# OBCv4_24.net
KiCad netlist of a schematic drawn in EAGLE
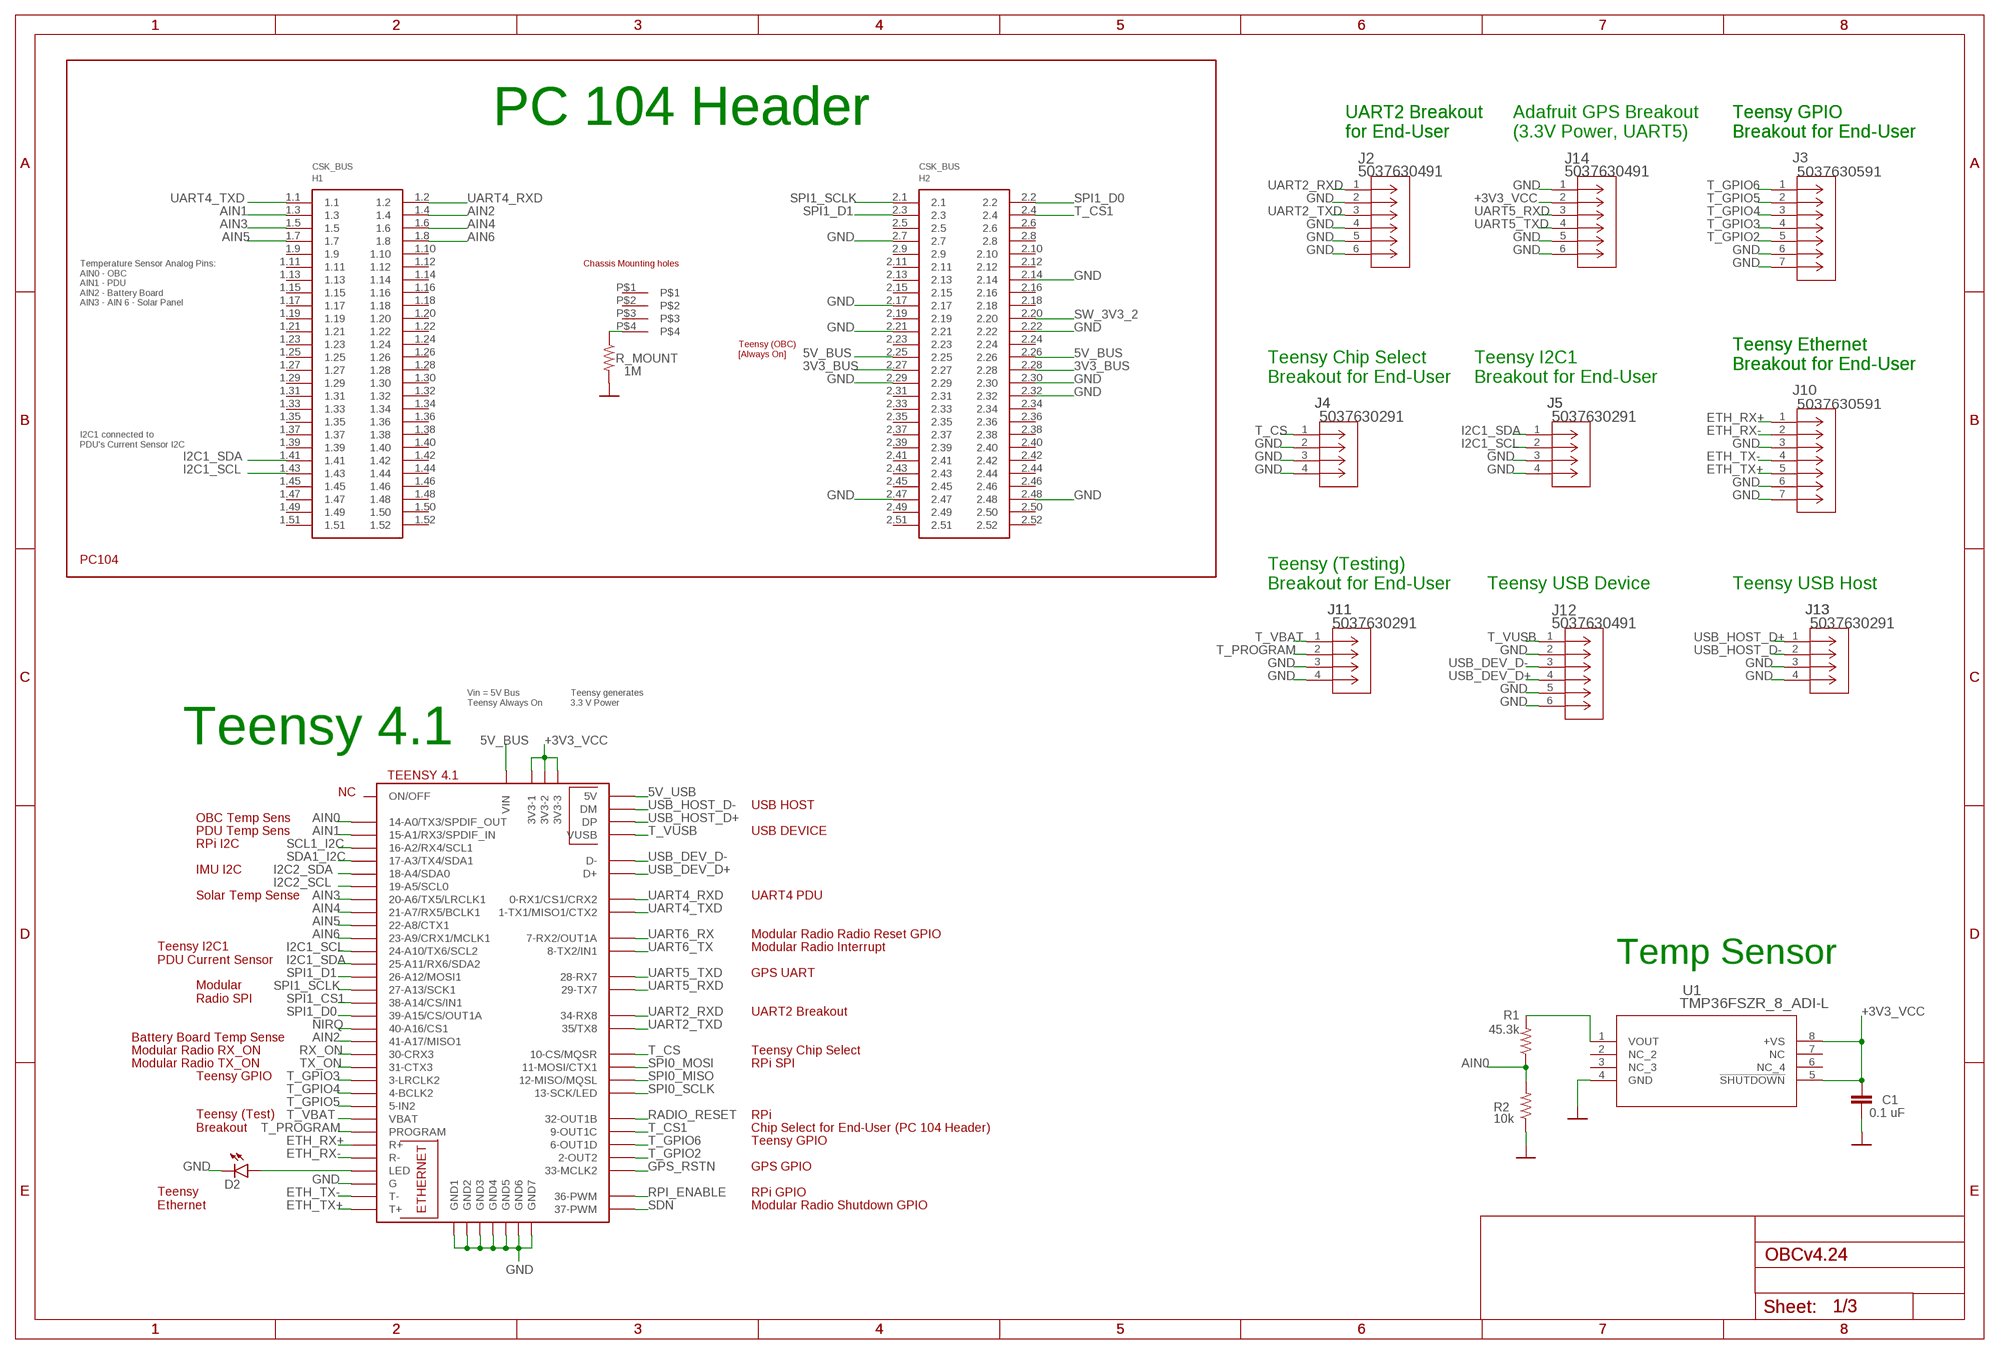
[diagram p0: schematic, sheet 1]
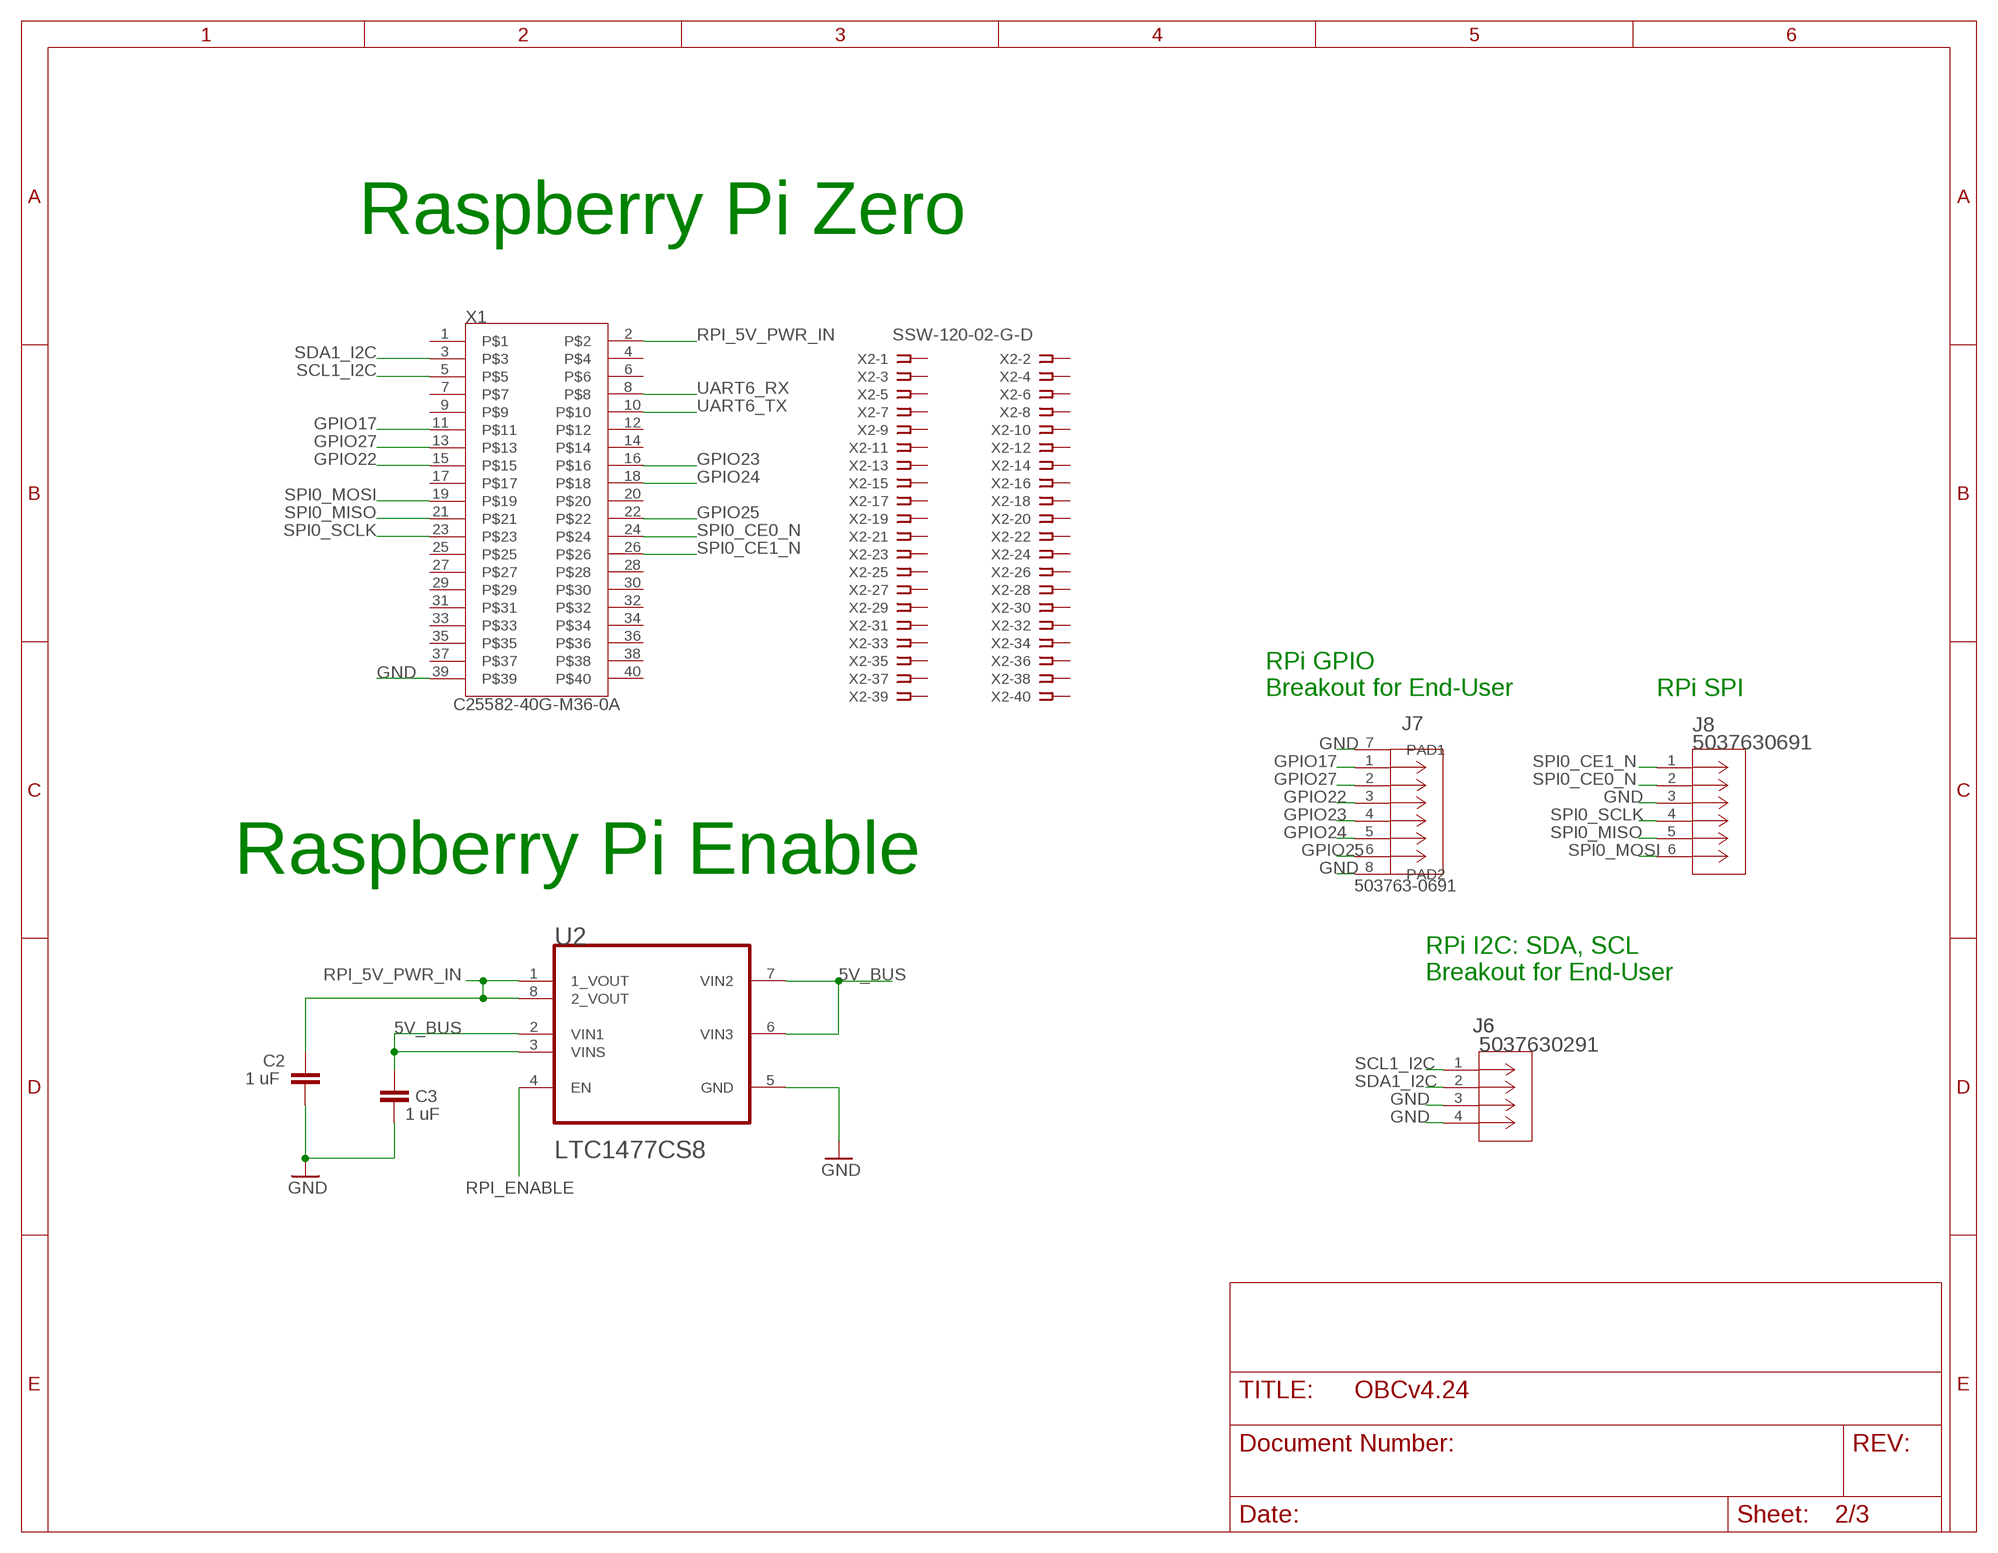
[diagram p1: schematic, sheet 2]
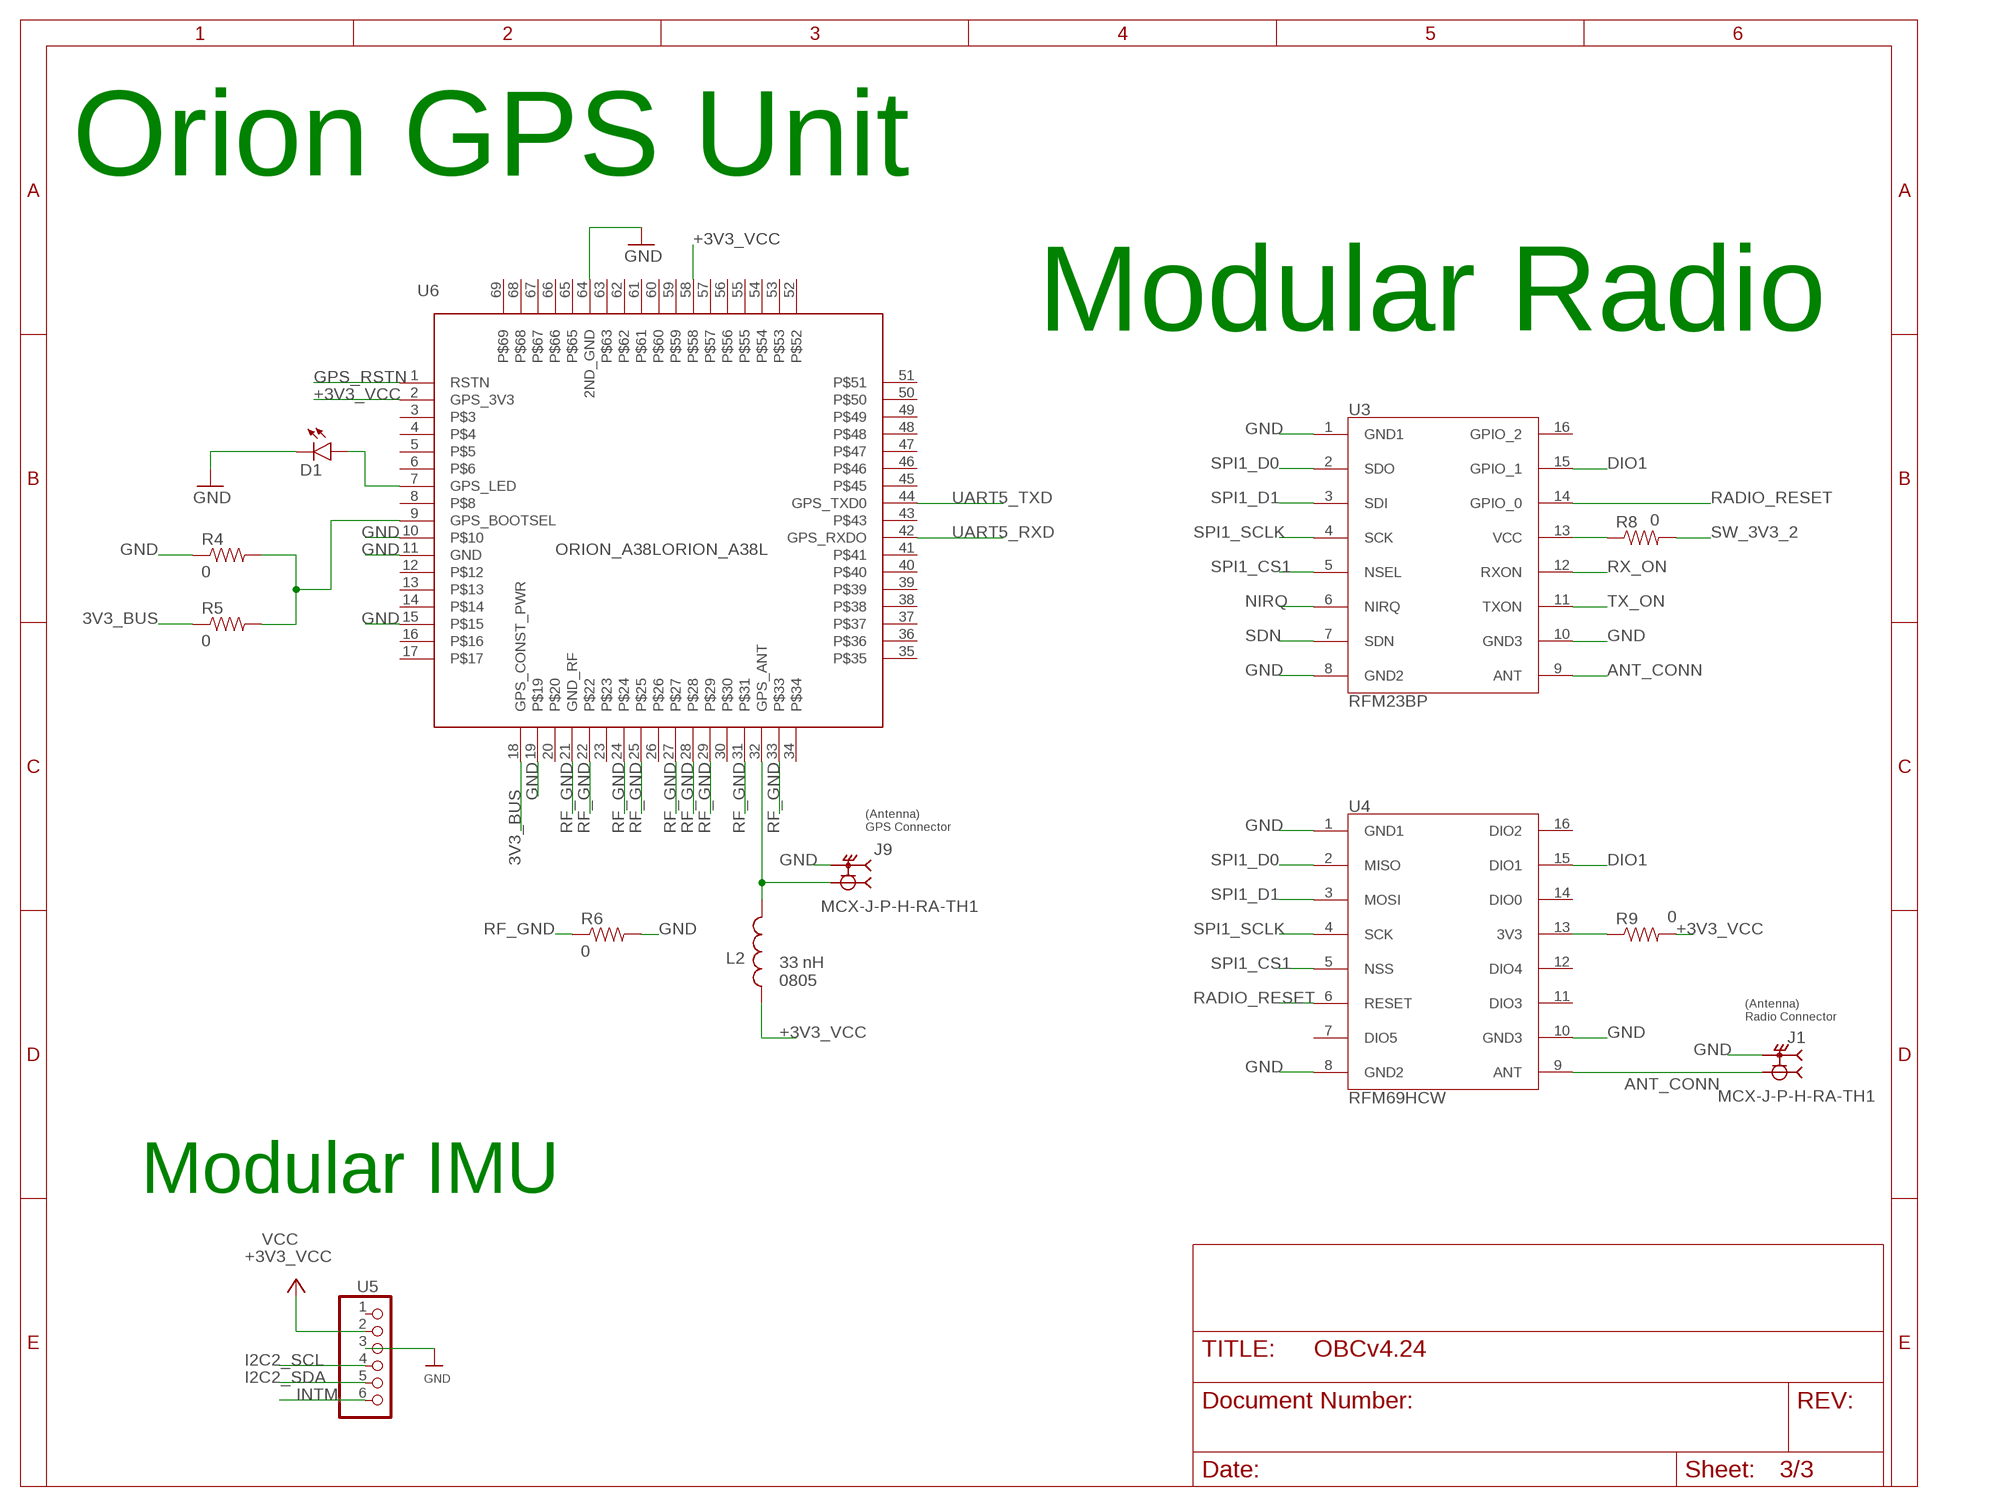
[diagram p2: schematic, sheet 3]

(export (version "E")
  (design (tool "Eeschema 10.0.6"))
  (components
    (comp (ref "D1")
      (value "LEDCHIP-LED0603")
      (footprint "eagle-import:CHIP-LED0603")
      (libsource (lib "eagle-import") (part "LEDCHIP-LED0603"))
    )
    (comp (ref "J1")
      (value "MCX-J-P-H-RA-TH1")
      (footprint "eagle-import:SAMTEC_MCX-J-P-H-RA-TH1")
      (fields (field (name "DIGI-KEY_PART_NUMBER") "SAM10607-ND") (field (name "MF") "Samtec"))
      (libsource (lib "eagle-import") (part "MCX-J-P-H-RA-TH1"))
    )
    (comp (ref "J9")
      (value "MCX-J-P-H-RA-TH1")
      (footprint "eagle-import:SAMTEC_MCX-J-P-H-RA-TH1")
      (fields (field (name "DIGI-KEY_PART_NUMBER") "SAM10607-ND") (field (name "MF") "Samtec"))
      (libsource (lib "eagle-import") (part "MCX-J-P-H-RA-TH1"))
    )
    (comp (ref "L2")
      (value "AIMC-0805-2N2S-T")
      (footprint "eagle-import:INDC2012X105N")
      (fields (field (name "DIGI-KEY_PART_NUMBER") "535-11562-1-ND") (field (name "MF") "Abracon"))
      (libsource (lib "eagle-import") (part "AIMC-0805-2N2S-T"))
    )
    (comp (ref "R4")
      (value "0")
      (footprint "eagle-import:0805")
      (libsource (lib "eagle-import") (part "RESISTOR0805-RES"))
    )
    (comp (ref "R5")
      (value "0")
      (footprint "eagle-import:0805")
      (libsource (lib "eagle-import") (part "RESISTOR0805-RES"))
    )
    (comp (ref "R6")
      (value "0")
      (footprint "eagle-import:0805")
      (libsource (lib "eagle-import") (part "RESISTOR0805-RES"))
    )
    (comp (ref "R8")
      (value "0")
      (footprint "eagle-import:R2512")
      (libsource (lib "eagle-import") (part "RESISTOR2512"))
    )
    (comp (ref "R9")
      (value "0")
      (footprint "eagle-import:R2512")
      (libsource (lib "eagle-import") (part "RESISTOR2512"))
    )
    (comp (ref "U3")
      (value "RFM23BP")
      (footprint "eagle-import:RFM23BP")
      (libsource (lib "eagle-import") (part "RFM23BP"))
    )
    (comp (ref "U4")
      (value "RFM69HCW")
      (footprint "eagle-import:RFM69HCW")
      (libsource (lib "eagle-import") (part "RFM69HCW"))
    )
    (comp (ref "U5")
      (value "HEADER-1X670MIL")
      (footprint "eagle-import:1X06_ROUND_70")
      (libsource (lib "eagle-import") (part "HEADER-1X670MIL"))
    )
    (comp (ref "U6")
      (value "ORION_A38LORION_A38L")
      (footprint "eagle-import:ORION_A38L")
      (libsource (lib "eagle-import") (part "ORION_A38LORION_A38L"))
    )
    (comp (ref "C1")
      (value "0.1 uF")
      (footprint "eagle-import:0805")
      (libsource (lib "eagle-import") (part "CAP0805"))
    )
    (comp (ref "D2")
      (value "LEDCHIP-LED0603")
      (footprint "eagle-import:CHIP-LED0603")
      (libsource (lib "eagle-import") (part "LEDCHIP-LED0603"))
    )
    (comp (ref "H1")
      (value "PC104_WCONN")
      (footprint "eagle-import:PC104_WCONN")
      (libsource (lib "eagle-import") (part "PC104_WCONN"))
    )
    (comp (ref "J2")
      (value "5037630491")
      (footprint "eagle-import:CON_5037630491")
      (fields (field (name "COPYRIGHT") "Copyright (C) 2018 Accelerated Designs. All rights reserved"))
      (libsource (lib "eagle-import") (part "5037630491"))
    )
    (comp (ref "J3")
      (value "5037630591")
      (footprint "eagle-import:CON_5037630591")
      (fields (field (name "COPYRIGHT") "Copyright (C) 2021 Ultra Librarian. All rights reserved."))
      (libsource (lib "eagle-import") (part "5037630591"))
    )
    (comp (ref "J4")
      (value "5037630291")
      (footprint "eagle-import:CON_5037630291")
      (fields (field (name "COPYRIGHT") "Copyright (C) 2018 Accelerated Designs. All rights reserved"))
      (libsource (lib "eagle-import") (part "5037630291"))
    )
    (comp (ref "J5")
      (value "5037630291")
      (footprint "eagle-import:CON_5037630291")
      (fields (field (name "COPYRIGHT") "Copyright (C) 2018 Accelerated Designs. All rights reserved"))
      (libsource (lib "eagle-import") (part "5037630291"))
    )
    (comp (ref "J10")
      (value "5037630591")
      (footprint "eagle-import:CON_5037630591")
      (fields (field (name "COPYRIGHT") "Copyright (C) 2021 Ultra Librarian. All rights reserved."))
      (libsource (lib "eagle-import") (part "5037630591"))
    )
    (comp (ref "J11")
      (value "5037630291")
      (footprint "eagle-import:CON_5037630291")
      (fields (field (name "COPYRIGHT") "Copyright (C) 2018 Accelerated Designs. All rights reserved"))
      (libsource (lib "eagle-import") (part "5037630291"))
    )
    (comp (ref "J12")
      (value "5037630491")
      (footprint "eagle-import:CON_5037630491")
      (fields (field (name "COPYRIGHT") "Copyright (C) 2018 Accelerated Designs. All rights reserved"))
      (libsource (lib "eagle-import") (part "5037630491"))
    )
    (comp (ref "J13")
      (value "5037630291")
      (footprint "eagle-import:CON_5037630291")
      (fields (field (name "COPYRIGHT") "Copyright (C) 2018 Accelerated Designs. All rights reserved"))
      (libsource (lib "eagle-import") (part "5037630291"))
    )
    (comp (ref "J14")
      (value "5037630491")
      (footprint "eagle-import:CON_5037630491")
      (fields (field (name "COPYRIGHT") "Copyright (C) 2018 Accelerated Designs. All rights reserved"))
      (libsource (lib "eagle-import") (part "5037630491"))
    )
    (comp (ref "R1")
      (value "45.3k")
      (footprint "eagle-import:0805")
      (libsource (lib "eagle-import") (part "RESISTOR0805-RES"))
    )
    (comp (ref "R2")
      (value "10k")
      (footprint "eagle-import:0805")
      (libsource (lib "eagle-import") (part "RESISTOR0805-RES"))
    )
    (comp (ref "R_MOUNT")
      (value "1M")
      (footprint "eagle-import:0805")
      (libsource (lib "eagle-import") (part "RESISTOR0805-RES"))
    )
    (comp (ref "U$1")
      (value "TEENSY41TEENSY")
      (footprint "eagle-import:TEENSY41")
      (libsource (lib "eagle-import") (part "TEENSY41TEENSY"))
    )
    (comp (ref "U1")
      (value "TMP36FSZR_8_ADI-L")
      (footprint "eagle-import:R_8_ADI-L")
      (fields
        (field (name "MANUFACTURER_PART_NUMBER") "TMP36FSZ")
        (field (name "COPYRIGHT") "Copyright (C) 2021 Ultra Librarian. All rights reserved.")
      )
      (libsource (lib "eagle-import") (part "TMP36FSZR_8_ADI-L"))
    )
    (comp (ref "C2")
      (value "1 uF")
      (footprint "eagle-import:0805")
      (libsource (lib "eagle-import") (part "CAP0805"))
    )
    (comp (ref "C3")
      (value "1 uF")
      (footprint "eagle-import:0805")
      (libsource (lib "eagle-import") (part "CAP0805"))
    )
    (comp (ref "J6")
      (value "5037630291")
      (footprint "eagle-import:CON_5037630291")
      (fields (field (name "COPYRIGHT") "Copyright (C) 2018 Accelerated Designs. All rights reserved"))
      (libsource (lib "eagle-import") (part "5037630291"))
    )
    (comp (ref "J7")
      (value "503763-0691")
      (footprint "eagle-import:CONN_503763-0691_MOL")
      (fields (field (name "COPYRIGHT") "Copyright (C) 2018 Accelerated Designs. All rights reserved"))
      (libsource (lib "eagle-import") (part "503763-0691"))
    )
    (comp (ref "J8")
      (value "5037630691")
      (footprint "eagle-import:CONN_503763-0691_MOL")
      (fields
        (field (name "MANUFACTURER_PART_NUMBER") "503763-0691")
        (field (name "COPYRIGHT") "Copyright (C) 2018 Accelerated Designs. All rights reserved")
      )
      (libsource (lib "eagle-import") (part "5037630691"))
    )
    (comp (ref "U2")
      (value "LTC1477CS8LINEAR_TECHNOLOGY_LTC1477CS8_0_2")
      (footprint "eagle-import:LINEAR_TECHNOLOGY_LTC1477CS8_2")
      (fields (field (name "MF") "Linear Technology") (field (name "MPN") "LTC1477CS8"))
      (libsource (lib "eagle-import") (part "LTC1477CS8LINEAR_TECHNOLOGY_LTC1477CS8_0_2"))
    )
    (comp (ref "X1")
      (value "C25582-40G-M36-0A")
      (footprint "eagle-import:ADAFRUIT_C25582-40G-M36-0A_0")
      (libsource (lib "eagle-import") (part "C25582-40G-M36-0A"))
    )
    (comp (ref "X2")
      (value "SSW-120-02-G-D")
      (footprint "eagle-import:SSW-120-02-G-D")
      (fields (field (name "MF") "Samtec Inc."))
      (libsource (lib "eagle-import") (part "SSW-120-02-G-D"))
    )
  )
  (nets
    (net (code "1") (name "+3V3_VCC") (class "Default")
      (node (ref "C1") (pin "1") (pinfunction "1_1") (pintype "passive"))
      (node (ref "J14") (pin "2") (pinfunction "2_2") (pintype "passive"))
      (node (ref "L2") (pin "1") (pinfunction "1_1") (pintype "passive"))
      (node (ref "R9") (pin "2") (pinfunction "2_2") (pintype "passive"))
      (node (ref "U$1") (pin "3V3-1") (pinfunction "3V3-1_3V3-1") (pintype "bidirectional"))
      (node (ref "U$1") (pin "3V3-2") (pinfunction "3V3-2_3V3-2") (pintype "bidirectional"))
      (node (ref "U$1") (pin "3V3-3") (pinfunction "3V3-3_3V3-3") (pintype "bidirectional"))
      (node (ref "U1") (pin "5") (pinfunction "~{SHUTDOWN}_5") (pintype "passive"))
      (node (ref "U1") (pin "8") (pinfunction "+VS_8") (pintype "power_in"))
      (node (ref "U5") (pin "2") (pinfunction "2_2") (pintype "passive"))
      (node (ref "U6") (pin "2") (pinfunction "GPS_3V3_2") (pintype "bidirectional"))
      (node (ref "U6") (pin "58") (pinfunction "P$58_58") (pintype "bidirectional"))
    )
    (net (code "2") (name "3V3_BUS") (class "Default")
      (node (ref "H1") (pin "2.27") (pinfunction "2.27_2.27") (pintype "bidirectional"))
      (node (ref "H1") (pin "2.28") (pinfunction "2.28_2.28") (pintype "bidirectional"))
      (node (ref "R5") (pin "1") (pinfunction "1_1") (pintype "passive"))
      (node (ref "U6") (pin "18") (pinfunction "GPS_CONST_PWR_18") (pintype "bidirectional"))
    )
    (net (code "3") (name "5V_BUS") (class "Default")
      (node (ref "C3") (pin "1") (pinfunction "1_1") (pintype "passive"))
      (node (ref "H1") (pin "2.25") (pinfunction "2.25_2.25") (pintype "bidirectional"))
      (node (ref "H1") (pin "2.26") (pinfunction "2.26_2.26") (pintype "bidirectional"))
      (node (ref "U$1") (pin "VIN") (pinfunction "VIN_VIN") (pintype "bidirectional"))
      (node (ref "U2") (pin "2") (pinfunction "VIN1_2") (pintype "power_in"))
      (node (ref "U2") (pin "3") (pinfunction "VINS_3") (pintype "power_in"))
      (node (ref "U2") (pin "6") (pinfunction "VIN3_6") (pintype "power_in"))
      (node (ref "U2") (pin "7") (pinfunction "VIN2_7") (pintype "power_in"))
    )
    (net (code "4") (name "5V_USB") (class "Default")
      (node (ref "U$1") (pin "+5V") (pinfunction "5V_+5V") (pintype "bidirectional"))
    )
    (net (code "5") (name "AIN0") (class "Default")
      (node (ref "R1") (pin "1") (pinfunction "1_1") (pintype "passive"))
      (node (ref "R2") (pin "2") (pinfunction "2_2") (pintype "passive"))
      (node (ref "U$1") (pin "14-A0/TX3/SPDIF_OUT") (pinfunction "14-A0/TX3/SPDIF_OUT_14-A0/TX3/SPDIF_OUT") (pintype "bidirectional"))
    )
    (net (code "6") (name "AIN1") (class "Default")
      (node (ref "H1") (pin "1.3") (pinfunction "1.3_1.3") (pintype "bidirectional"))
      (node (ref "U$1") (pin "15-A1/RX3/SPDIF_IN") (pinfunction "15-A1/RX3/SPDIF_IN_15-A1/RX3/SPDIF_IN") (pintype "bidirectional"))
    )
    (net (code "7") (name "AIN2") (class "Default")
      (node (ref "H1") (pin "1.4") (pinfunction "1.4_1.4") (pintype "bidirectional"))
      (node (ref "U$1") (pin "41-A17/MISO1") (pinfunction "41-A17/MISO1_41-A17/MISO1") (pintype "bidirectional"))
    )
    (net (code "8") (name "AIN3") (class "Default")
      (node (ref "H1") (pin "1.5") (pinfunction "1.5_1.5") (pintype "bidirectional"))
      (node (ref "U$1") (pin "20-A6/TX5/LRCLK1") (pinfunction "20-A6/TX5/LRCLK1_20-A6/TX5/LRCLK1") (pintype "bidirectional"))
    )
    (net (code "9") (name "AIN4") (class "Default")
      (node (ref "H1") (pin "1.6") (pinfunction "1.6_1.6") (pintype "bidirectional"))
      (node (ref "U$1") (pin "21-A7/RX5/BCLK1") (pinfunction "21-A7/RX5/BCLK1_21-A7/RX5/BCLK1") (pintype "bidirectional"))
    )
    (net (code "10") (name "AIN5") (class "Default")
      (node (ref "H1") (pin "1.7") (pinfunction "1.7_1.7") (pintype "bidirectional"))
      (node (ref "U$1") (pin "22-A8/CTX1") (pinfunction "22-A8/CTX1_22-A8/CTX1") (pintype "bidirectional"))
    )
    (net (code "11") (name "AIN6") (class "Default")
      (node (ref "H1") (pin "1.8") (pinfunction "1.8_1.8") (pintype "bidirectional"))
      (node (ref "U$1") (pin "23-A9/CRX1/MCLK1") (pinfunction "23-A9/CRX1/MCLK1_23-A9/CRX1/MCLK1") (pintype "bidirectional"))
    )
    (net (code "12") (name "ANT_CONN") (class "Default")
      (node (ref "J1") (pin "1") (pinfunction "1_1") (pintype "passive"))
      (node (ref "U3") (pin "9") (pinfunction "ANT_9") (pintype "bidirectional"))
      (node (ref "U4") (pin "9") (pinfunction "ANT_9") (pintype "bidirectional"))
    )
    (net (code "13") (name "DIO1") (class "Default")
      (node (ref "U3") (pin "15") (pinfunction "GPIO_1_15") (pintype "bidirectional"))
      (node (ref "U4") (pin "15") (pinfunction "DIO1_15") (pintype "bidirectional"))
    )
    (net (code "14") (name "ETH_RX+") (class "Default")
      (node (ref "J10") (pin "1") (pinfunction "1_1") (pintype "passive"))
      (node (ref "U$1") (pin "R+") (pinfunction "R+_R+") (pintype "bidirectional"))
    )
    (net (code "15") (name "ETH_RX-") (class "Default")
      (node (ref "J10") (pin "2") (pinfunction "2_2") (pintype "passive"))
      (node (ref "U$1") (pin "R-") (pinfunction "R-_R-") (pintype "bidirectional"))
    )
    (net (code "16") (name "ETH_TX+") (class "Default")
      (node (ref "J10") (pin "5") (pinfunction "5_5") (pintype "passive"))
      (node (ref "U$1") (pin "T+") (pinfunction "T+_T+") (pintype "bidirectional"))
    )
    (net (code "17") (name "ETH_TX-") (class "Default")
      (node (ref "J10") (pin "4") (pinfunction "4_4") (pintype "passive"))
      (node (ref "U$1") (pin "T-") (pinfunction "T-_T-") (pintype "bidirectional"))
    )
    (net (code "18") (name "GND") (class "Default")
      (node (ref "C1") (pin "2") (pinfunction "2_2") (pintype "passive"))
      (node (ref "C2") (pin "2") (pinfunction "2_2") (pintype "passive"))
      (node (ref "C3") (pin "2") (pinfunction "2_2") (pintype "passive"))
      (node (ref "D1") (pin "C") (pinfunction "C_C") (pintype "passive"))
      (node (ref "D2") (pin "C") (pinfunction "C_C") (pintype "passive"))
      (node (ref "H1") (pin "2.14") (pinfunction "2.14_2.14") (pintype "bidirectional"))
      (node (ref "H1") (pin "2.17") (pinfunction "2.17_2.17") (pintype "bidirectional"))
      (node (ref "H1") (pin "2.21") (pinfunction "2.21_2.21") (pintype "bidirectional"))
      (node (ref "H1") (pin "2.22") (pinfunction "2.22_2.22") (pintype "bidirectional"))
      (node (ref "H1") (pin "2.29") (pinfunction "2.29_2.29") (pintype "bidirectional"))
      (node (ref "H1") (pin "2.30") (pinfunction "2.30_2.30") (pintype "bidirectional"))
      (node (ref "H1") (pin "2.32") (pinfunction "2.32_2.32") (pintype "bidirectional"))
      (node (ref "H1") (pin "2.47") (pinfunction "2.47_2.47") (pintype "bidirectional"))
      (node (ref "H1") (pin "2.48") (pinfunction "2.48_2.48") (pintype "bidirectional"))
      (node (ref "H1") (pin "2.7") (pinfunction "2.7_2.7") (pintype "bidirectional"))
      (node (ref "J1") (pin "S1") (pinfunction "2_S1") (pintype "passive"))
      (node (ref "J1") (pin "S2") (pinfunction "2_S2") (pintype "passive"))
      (node (ref "J1") (pin "S3") (pinfunction "2_S3") (pintype "passive"))
      (node (ref "J1") (pin "S4") (pinfunction "2_S4") (pintype "passive"))
      (node (ref "J10") (pin "3") (pinfunction "3_3") (pintype "passive"))
      (node (ref "J10") (pin "6") (pinfunction "6_6") (pintype "passive"))
      (node (ref "J10") (pin "7") (pinfunction "7_7") (pintype "passive"))
      (node (ref "J11") (pin "3") (pinfunction "3_3") (pintype "passive"))
      (node (ref "J11") (pin "4") (pinfunction "4_4") (pintype "passive"))
      (node (ref "J12") (pin "2") (pinfunction "2_2") (pintype "passive"))
      (node (ref "J12") (pin "5") (pinfunction "5_5") (pintype "passive"))
      (node (ref "J12") (pin "6") (pinfunction "6_6") (pintype "passive"))
      (node (ref "J13") (pin "3") (pinfunction "3_3") (pintype "passive"))
      (node (ref "J13") (pin "4") (pinfunction "4_4") (pintype "passive"))
      (node (ref "J14") (pin "1") (pinfunction "1_1") (pintype "passive"))
      (node (ref "J14") (pin "5") (pinfunction "5_5") (pintype "passive"))
      (node (ref "J14") (pin "6") (pinfunction "6_6") (pintype "passive"))
      (node (ref "J2") (pin "2") (pinfunction "2_2") (pintype "passive"))
      (node (ref "J2") (pin "4") (pinfunction "4_4") (pintype "passive"))
      (node (ref "J2") (pin "5") (pinfunction "5_5") (pintype "passive"))
      (node (ref "J2") (pin "6") (pinfunction "6_6") (pintype "passive"))
      (node (ref "J3") (pin "6") (pinfunction "6_6") (pintype "passive"))
      (node (ref "J3") (pin "7") (pinfunction "7_7") (pintype "passive"))
      (node (ref "J4") (pin "2") (pinfunction "2_2") (pintype "passive"))
      (node (ref "J4") (pin "3") (pinfunction "3_3") (pintype "passive"))
      (node (ref "J4") (pin "4") (pinfunction "4_4") (pintype "passive"))
      (node (ref "J5") (pin "3") (pinfunction "3_3") (pintype "passive"))
      (node (ref "J5") (pin "4") (pinfunction "4_4") (pintype "passive"))
      (node (ref "J6") (pin "3") (pinfunction "3_3") (pintype "passive"))
      (node (ref "J6") (pin "4") (pinfunction "4_4") (pintype "passive"))
      (node (ref "J7") (pin "7") (pinfunction "PAD1_7") (pintype "bidirectional"))
      (node (ref "J7") (pin "8") (pinfunction "PAD2_8") (pintype "bidirectional"))
      (node (ref "J8") (pin "3") (pinfunction "3_3") (pintype "passive"))
      (node (ref "J9") (pin "S1") (pinfunction "2_S1") (pintype "passive"))
      (node (ref "J9") (pin "S2") (pinfunction "2_S2") (pintype "passive"))
      (node (ref "J9") (pin "S3") (pinfunction "2_S3") (pintype "passive"))
      (node (ref "J9") (pin "S4") (pinfunction "2_S4") (pintype "passive"))
      (node (ref "R2") (pin "1") (pinfunction "1_1") (pintype "passive"))
      (node (ref "R4") (pin "1") (pinfunction "1_1") (pintype "passive"))
      (node (ref "R6") (pin "2") (pinfunction "2_2") (pintype "passive"))
      (node (ref "R_MOUNT") (pin "2") (pinfunction "2_2") (pintype "passive"))
      (node (ref "U$1") (pin "G") (pinfunction "G_G") (pintype "bidirectional"))
      (node (ref "U$1") (pin "GND") (pinfunction "GND7_GND") (pintype "bidirectional"))
      (node (ref "U$1") (pin "GND1") (pinfunction "GND1_GND1") (pintype "bidirectional"))
      (node (ref "U$1") (pin "GND2") (pinfunction "GND2_GND2") (pintype "bidirectional"))
      (node (ref "U$1") (pin "GND3") (pinfunction "GND3_GND3") (pintype "bidirectional"))
      (node (ref "U$1") (pin "GND4") (pinfunction "GND4_GND4") (pintype "bidirectional"))
      (node (ref "U$1") (pin "GND5") (pinfunction "GND5_GND5") (pintype "bidirectional"))
      (node (ref "U$1") (pin "GND6") (pinfunction "GND6_GND6") (pintype "bidirectional"))
      (node (ref "U1") (pin "4") (pinfunction "GND_4") (pintype "passive"))
      (node (ref "U2") (pin "5") (pinfunction "GND_5") (pintype "power_in"))
      (node (ref "U3") (pin "1") (pinfunction "GND1_1") (pintype "bidirectional"))
      (node (ref "U3") (pin "10") (pinfunction "GND3_10") (pintype "bidirectional"))
      (node (ref "U3") (pin "8") (pinfunction "GND2_8") (pintype "bidirectional"))
      (node (ref "U4") (pin "1") (pinfunction "GND1_1") (pintype "bidirectional"))
      (node (ref "U4") (pin "10") (pinfunction "GND3_10") (pintype "bidirectional"))
      (node (ref "U4") (pin "8") (pinfunction "GND2_8") (pintype "bidirectional"))
      (node (ref "U5") (pin "3") (pinfunction "3_3") (pintype "passive"))
      (node (ref "U6") (pin "10") (pinfunction "P$10_10") (pintype "bidirectional"))
      (node (ref "U6") (pin "11") (pinfunction "GND_11") (pintype "bidirectional"))
      (node (ref "U6") (pin "15") (pinfunction "P$15_15") (pintype "bidirectional"))
      (node (ref "U6") (pin "19") (pinfunction "P$19_19") (pintype "bidirectional"))
      (node (ref "U6") (pin "64") (pinfunction "2ND_GND_64") (pintype "bidirectional"))
      (node (ref "X1") (pin "39") (pinfunction "P$39_39") (pintype "bidirectional"))
    )
    (net (code "19") (name "GPIO17") (class "Default")
      (node (ref "J7") (pin "1") (pinfunction "1_1") (pintype "passive"))
      (node (ref "X1") (pin "11") (pinfunction "P$11_11") (pintype "bidirectional"))
    )
    (net (code "20") (name "GPIO22") (class "Default")
      (node (ref "J7") (pin "3") (pinfunction "3_3") (pintype "passive"))
      (node (ref "X1") (pin "15") (pinfunction "P$15_15") (pintype "bidirectional"))
    )
    (net (code "21") (name "GPIO23") (class "Default")
      (node (ref "J7") (pin "4") (pinfunction "4_4") (pintype "passive"))
      (node (ref "X1") (pin "16") (pinfunction "P$16_16") (pintype "bidirectional"))
    )
    (net (code "22") (name "GPIO24") (class "Default")
      (node (ref "J7") (pin "5") (pinfunction "5_5") (pintype "passive"))
      (node (ref "X1") (pin "18") (pinfunction "P$18_18") (pintype "bidirectional"))
    )
    (net (code "23") (name "GPIO25") (class "Default")
      (node (ref "J7") (pin "6") (pinfunction "6_6") (pintype "passive"))
      (node (ref "X1") (pin "22") (pinfunction "P$22_22") (pintype "bidirectional"))
    )
    (net (code "24") (name "GPIO27") (class "Default")
      (node (ref "J7") (pin "2") (pinfunction "2_2") (pintype "passive"))
      (node (ref "X1") (pin "13") (pinfunction "P$13_13") (pintype "bidirectional"))
    )
    (net (code "25") (name "GPS_RSTN") (class "Default")
      (node (ref "U$1") (pin "33-MCLK2") (pinfunction "33-MCLK2_33-MCLK2") (pintype "bidirectional"))
      (node (ref "U6") (pin "1") (pinfunction "RSTN_1") (pintype "bidirectional"))
    )
    (net (code "26") (name "I2C1_SCL") (class "Default")
      (node (ref "H1") (pin "1.43") (pinfunction "1.43_1.43") (pintype "bidirectional"))
      (node (ref "J5") (pin "2") (pinfunction "2_2") (pintype "passive"))
      (node (ref "U$1") (pin "24-A10/TX6/SCL2") (pinfunction "24-A10/TX6/SCL2_24-A10/TX6/SCL2") (pintype "bidirectional"))
    )
    (net (code "27") (name "I2C1_SDA") (class "Default")
      (node (ref "H1") (pin "1.41") (pinfunction "1.41_1.41") (pintype "bidirectional"))
      (node (ref "J5") (pin "1") (pinfunction "1_1") (pintype "passive"))
      (node (ref "U$1") (pin "25-A11/RX6/SDA2") (pinfunction "25-A11/RX6/SDA2_25-A11/RX6/SDA2") (pintype "bidirectional"))
    )
    (net (code "28") (name "I2C2_SCL") (class "Default")
      (node (ref "U$1") (pin "19-A5/SCL0") (pinfunction "19-A5/SCL0_19-A5/SCL0") (pintype "bidirectional"))
      (node (ref "U5") (pin "4") (pinfunction "4_4") (pintype "passive"))
    )
    (net (code "29") (name "I2C2_SDA") (class "Default")
      (node (ref "U$1") (pin "18-A4/SDA0") (pinfunction "18-A4/SDA0_18-A4/SDA0") (pintype "bidirectional"))
      (node (ref "U5") (pin "5") (pinfunction "5_5") (pintype "passive"))
    )
    (net (code "30") (name "INTM") (class "Default")
      (node (ref "U5") (pin "6") (pinfunction "6_6") (pintype "passive"))
    )
    (net (code "31") (name "NIRQ") (class "Default")
      (node (ref "U$1") (pin "40-A16/CS1") (pinfunction "40-A16/CS1_40-A16/CS1") (pintype "bidirectional"))
      (node (ref "U3") (pin "6") (pinfunction "NIRQ_6") (pintype "bidirectional"))
    )
    (net (code "32") (name "Net-(D2-PadA)") (class "Default")
      (node (ref "D2") (pin "A") (pinfunction "A_A") (pintype "passive"))
      (node (ref "U$1") (pin "LED") (pinfunction "LED_LED") (pintype "bidirectional"))
    )
    (net (code "33") (name "Net-(H1-PadP$4)") (class "Default")
      (node (ref "H1") (pin "P$4") (pinfunction "P$4_P$4") (pintype "bidirectional"))
      (node (ref "R_MOUNT") (pin "1") (pinfunction "1_1") (pintype "passive"))
    )
    (net (code "34") (name "Net-(U1-VOUT)") (class "Default")
      (node (ref "R1") (pin "2") (pinfunction "2_2") (pintype "passive"))
      (node (ref "U1") (pin "1") (pinfunction "VOUT_1") (pintype "output"))
    )
    (net (code "35") (name "Net-(U3-VCC)") (class "Default")
      (node (ref "R8") (pin "1") (pinfunction "1_1") (pintype "passive"))
      (node (ref "U3") (pin "13") (pinfunction "VCC_13") (pintype "bidirectional"))
    )
    (net (code "36") (name "Net-(U4-3V3)") (class "Default")
      (node (ref "R9") (pin "1") (pinfunction "1_1") (pintype "passive"))
      (node (ref "U4") (pin "13") (pinfunction "3V3_13") (pintype "bidirectional"))
    )
    (net (code "37") (name "Net-(U6-GPS_ANT)") (class "Default")
      (node (ref "J9") (pin "1") (pinfunction "1_1") (pintype "passive"))
      (node (ref "L2") (pin "2") (pinfunction "2_2") (pintype "passive"))
      (node (ref "U6") (pin "32") (pinfunction "GPS_ANT_32") (pintype "bidirectional"))
    )
    (net (code "38") (name "Net-(U6-GPS_BOOTSEL)") (class "Default")
      (node (ref "R4") (pin "2") (pinfunction "2_2") (pintype "passive"))
      (node (ref "R5") (pin "2") (pinfunction "2_2") (pintype "passive"))
      (node (ref "U6") (pin "9") (pinfunction "GPS_BOOTSEL_9") (pintype "bidirectional"))
    )
    (net (code "39") (name "Net-(U6-GPS_LED)") (class "Default")
      (node (ref "D1") (pin "A") (pinfunction "A_A") (pintype "passive"))
      (node (ref "U6") (pin "7") (pinfunction "GPS_LED_7") (pintype "bidirectional"))
    )
    (net (code "40") (name "RADIO_RESET") (class "Default")
      (node (ref "U$1") (pin "32-OUT1B") (pinfunction "32-OUT1B_32-OUT1B") (pintype "bidirectional"))
      (node (ref "U3") (pin "14") (pinfunction "GPIO_0_14") (pintype "bidirectional"))
      (node (ref "U4") (pin "6") (pinfunction "RESET_6") (pintype "bidirectional"))
    )
    (net (code "41") (name "RF_GND") (class "Default")
      (node (ref "R6") (pin "1") (pinfunction "1_1") (pintype "passive"))
      (node (ref "U6") (pin "21") (pinfunction "GND_RF_21") (pintype "bidirectional"))
      (node (ref "U6") (pin "22") (pinfunction "P$22_22") (pintype "bidirectional"))
      (node (ref "U6") (pin "24") (pinfunction "P$24_24") (pintype "bidirectional"))
      (node (ref "U6") (pin "25") (pinfunction "P$25_25") (pintype "bidirectional"))
      (node (ref "U6") (pin "27") (pinfunction "P$27_27") (pintype "bidirectional"))
      (node (ref "U6") (pin "28") (pinfunction "P$28_28") (pintype "bidirectional"))
      (node (ref "U6") (pin "29") (pinfunction "P$29_29") (pintype "bidirectional"))
      (node (ref "U6") (pin "31") (pinfunction "P$31_31") (pintype "bidirectional"))
      (node (ref "U6") (pin "33") (pinfunction "P$33_33") (pintype "bidirectional"))
    )
    (net (code "42") (name "RPI_5V_PWR_IN") (class "Default")
      (node (ref "C2") (pin "1") (pinfunction "1_1") (pintype "passive"))
      (node (ref "U2") (pin "1") (pinfunction "1_VOUT_1") (pintype "power_in"))
      (node (ref "U2") (pin "8") (pinfunction "2_VOUT_8") (pintype "power_in"))
      (node (ref "X1") (pin "2") (pinfunction "P$2_2") (pintype "bidirectional"))
    )
    (net (code "43") (name "RPI_ENABLE") (class "Default")
      (node (ref "U$1") (pin "36-PWM") (pinfunction "36-PWM_36-PWM") (pintype "bidirectional"))
      (node (ref "U2") (pin "4") (pinfunction "EN_4") (pintype "input"))
    )
    (net (code "44") (name "RX_ON") (class "Default")
      (node (ref "U$1") (pin "30-CRX3") (pinfunction "30-CRX3_30-CRX3") (pintype "bidirectional"))
      (node (ref "U3") (pin "12") (pinfunction "RXON_12") (pintype "bidirectional"))
    )
    (net (code "45") (name "SCL1_I2C") (class "Default")
      (node (ref "J6") (pin "1") (pinfunction "1_1") (pintype "passive"))
      (node (ref "U$1") (pin "16-A2/RX4/SCL1") (pinfunction "16-A2/RX4/SCL1_16-A2/RX4/SCL1") (pintype "bidirectional"))
      (node (ref "X1") (pin "5") (pinfunction "P$5_5") (pintype "bidirectional"))
    )
    (net (code "46") (name "SDA1_I2C") (class "Default")
      (node (ref "J6") (pin "2") (pinfunction "2_2") (pintype "passive"))
      (node (ref "U$1") (pin "17-A3/TX4/SDA1") (pinfunction "17-A3/TX4/SDA1_17-A3/TX4/SDA1") (pintype "bidirectional"))
      (node (ref "X1") (pin "3") (pinfunction "P$3_3") (pintype "bidirectional"))
    )
    (net (code "47") (name "SDN") (class "Default")
      (node (ref "U$1") (pin "37-PWM") (pinfunction "37-PWM_37-PWM") (pintype "bidirectional"))
      (node (ref "U3") (pin "7") (pinfunction "SDN_7") (pintype "bidirectional"))
    )
    (net (code "48") (name "SPI0_CE0_N") (class "Default")
      (node (ref "J8") (pin "2") (pinfunction "2_2") (pintype "passive"))
      (node (ref "X1") (pin "24") (pinfunction "P$24_24") (pintype "bidirectional"))
    )
    (net (code "49") (name "SPI0_CE1_N") (class "Default")
      (node (ref "J8") (pin "1") (pinfunction "1_1") (pintype "passive"))
      (node (ref "X1") (pin "26") (pinfunction "P$26_26") (pintype "bidirectional"))
    )
    (net (code "50") (name "SPI0_MISO") (class "Default")
      (node (ref "J8") (pin "5") (pinfunction "5_5") (pintype "passive"))
      (node (ref "U$1") (pin "12-MISO/MQSL") (pinfunction "12-MISO/MQSL_12-MISO/MQSL") (pintype "bidirectional"))
      (node (ref "X1") (pin "21") (pinfunction "P$21_21") (pintype "bidirectional"))
    )
    (net (code "51") (name "SPI0_MOSI") (class "Default")
      (node (ref "J8") (pin "6") (pinfunction "6_6") (pintype "passive"))
      (node (ref "U$1") (pin "11-MOSI/CTX1") (pinfunction "11-MOSI/CTX1_11-MOSI/CTX1") (pintype "bidirectional"))
      (node (ref "X1") (pin "19") (pinfunction "P$19_19") (pintype "bidirectional"))
    )
    (net (code "52") (name "SPI0_SCLK") (class "Default")
      (node (ref "J8") (pin "4") (pinfunction "4_4") (pintype "passive"))
      (node (ref "U$1") (pin "13-SCK/LED") (pinfunction "13-SCK/LED_13-SCK/LED") (pintype "bidirectional"))
      (node (ref "X1") (pin "23") (pinfunction "P$23_23") (pintype "bidirectional"))
    )
    (net (code "53") (name "SPI1_CS1") (class "Default")
      (node (ref "U$1") (pin "38-A14/CS/IN1") (pinfunction "38-A14/CS/IN1_38-A14/CS/IN1") (pintype "bidirectional"))
      (node (ref "U3") (pin "5") (pinfunction "NSEL_5") (pintype "bidirectional"))
      (node (ref "U4") (pin "5") (pinfunction "NSS_5") (pintype "bidirectional"))
    )
    (net (code "54") (name "SPI1_D0") (class "Default")
      (node (ref "H1") (pin "2.2") (pinfunction "2.2_2.2") (pintype "bidirectional"))
      (node (ref "U$1") (pin "39-A15/CS/OUT1A") (pinfunction "39-A15/CS/OUT1A_39-A15/CS/OUT1A") (pintype "bidirectional"))
      (node (ref "U3") (pin "2") (pinfunction "SDO_2") (pintype "bidirectional"))
      (node (ref "U4") (pin "2") (pinfunction "MISO_2") (pintype "bidirectional"))
    )
    (net (code "55") (name "SPI1_D1") (class "Default")
      (node (ref "H1") (pin "2.3") (pinfunction "2.3_2.3") (pintype "bidirectional"))
      (node (ref "U$1") (pin "26-A12/MOSI1") (pinfunction "26-A12/MOSI1_26-A12/MOSI1") (pintype "bidirectional"))
      (node (ref "U3") (pin "3") (pinfunction "SDI_3") (pintype "bidirectional"))
      (node (ref "U4") (pin "3") (pinfunction "MOSI_3") (pintype "bidirectional"))
    )
    (net (code "56") (name "SPI1_SCLK") (class "Default")
      (node (ref "H1") (pin "2.1") (pinfunction "2.1_2.1") (pintype "bidirectional"))
      (node (ref "U$1") (pin "27-A13/SCK1") (pinfunction "27-A13/SCK1_27-A13/SCK1") (pintype "bidirectional"))
      (node (ref "U3") (pin "4") (pinfunction "SCK_4") (pintype "bidirectional"))
      (node (ref "U4") (pin "4") (pinfunction "SCK_4") (pintype "bidirectional"))
    )
    (net (code "57") (name "SW_3V3_2") (class "Default")
      (node (ref "H1") (pin "2.20") (pinfunction "2.20_2.20") (pintype "bidirectional"))
      (node (ref "R8") (pin "2") (pinfunction "2_2") (pintype "passive"))
    )
    (net (code "58") (name "TX_ON") (class "Default")
      (node (ref "U$1") (pin "31-CTX3") (pinfunction "31-CTX3_31-CTX3") (pintype "bidirectional"))
      (node (ref "U3") (pin "11") (pinfunction "TXON_11") (pintype "bidirectional"))
    )
    (net (code "59") (name "T_CS") (class "Default")
      (node (ref "J4") (pin "1") (pinfunction "1_1") (pintype "passive"))
      (node (ref "U$1") (pin "10-CS\\MQSR") (pinfunction "10-CS/MQSR_10-CS\\MQSR") (pintype "bidirectional"))
    )
    (net (code "60") (name "T_CS1") (class "Default")
      (node (ref "H1") (pin "2.4") (pinfunction "2.4_2.4") (pintype "bidirectional"))
      (node (ref "U$1") (pin "9-OUT1C") (pinfunction "9-OUT1C_9-OUT1C") (pintype "bidirectional"))
    )
    (net (code "61") (name "T_GPIO2") (class "Default")
      (node (ref "J3") (pin "5") (pinfunction "5_5") (pintype "passive"))
      (node (ref "U$1") (pin "2-OUT2") (pinfunction "2-OUT2_2-OUT2") (pintype "bidirectional"))
    )
    (net (code "62") (name "T_GPIO3") (class "Default")
      (node (ref "J3") (pin "4") (pinfunction "4_4") (pintype "passive"))
      (node (ref "U$1") (pin "3-LRCLK2") (pinfunction "3-LRCLK2_3-LRCLK2") (pintype "bidirectional"))
    )
    (net (code "63") (name "T_GPIO4") (class "Default")
      (node (ref "J3") (pin "3") (pinfunction "3_3") (pintype "passive"))
      (node (ref "U$1") (pin "4-BCLK2") (pinfunction "4-BCLK2_4-BCLK2") (pintype "bidirectional"))
    )
    (net (code "64") (name "T_GPIO5") (class "Default")
      (node (ref "J3") (pin "2") (pinfunction "2_2") (pintype "passive"))
      (node (ref "U$1") (pin "5-IN2") (pinfunction "5-IN2_5-IN2") (pintype "bidirectional"))
    )
    (net (code "65") (name "T_GPIO6") (class "Default")
      (node (ref "J3") (pin "1") (pinfunction "1_1") (pintype "passive"))
      (node (ref "U$1") (pin "6-OUT1D") (pinfunction "6-OUT1D_6-OUT1D") (pintype "bidirectional"))
    )
    (net (code "66") (name "T_PROGRAM") (class "Default")
      (node (ref "J11") (pin "2") (pinfunction "2_2") (pintype "passive"))
      (node (ref "U$1") (pin "PROGRAM") (pinfunction "PROGRAM_PROGRAM") (pintype "bidirectional"))
    )
    (net (code "67") (name "T_VBAT") (class "Default")
      (node (ref "J11") (pin "1") (pinfunction "1_1") (pintype "passive"))
      (node (ref "U$1") (pin "VBAT") (pinfunction "VBAT_VBAT") (pintype "bidirectional"))
    )
    (net (code "68") (name "T_VUSB") (class "Default")
      (node (ref "J12") (pin "1") (pinfunction "1_1") (pintype "passive"))
      (node (ref "U$1") (pin "VUSB") (pinfunction "VUSB_VUSB") (pintype "bidirectional"))
    )
    (net (code "69") (name "UART2_RXD") (class "Default")
      (node (ref "J2") (pin "1") (pinfunction "1_1") (pintype "passive"))
      (node (ref "U$1") (pin "34-RX8") (pinfunction "34-RX8_34-RX8") (pintype "bidirectional"))
    )
    (net (code "70") (name "UART2_TXD") (class "Default")
      (node (ref "J2") (pin "3") (pinfunction "3_3") (pintype "passive"))
      (node (ref "U$1") (pin "35-TX8") (pinfunction "35/TX8_35-TX8") (pintype "bidirectional"))
    )
    (net (code "71") (name "UART4_RXD") (class "Default")
      (node (ref "H1") (pin "1.2") (pinfunction "1.2_1.2") (pintype "bidirectional"))
      (node (ref "U$1") (pin "0-RX1/CS1/CRX2") (pinfunction "0-RX1/CS1/CRX2_0-RX1/CS1/CRX2") (pintype "bidirectional"))
    )
    (net (code "72") (name "UART4_TXD") (class "Default")
      (node (ref "H1") (pin "1.1") (pinfunction "1.1_1.1") (pintype "bidirectional"))
      (node (ref "U$1") (pin "1-TX1/MISO1/CTX2") (pinfunction "1-TX1/MISO1/CTX2_1-TX1/MISO1/CTX2") (pintype "bidirectional"))
    )
    (net (code "73") (name "UART5_RXD") (class "Default")
      (node (ref "J14") (pin "3") (pinfunction "3_3") (pintype "passive"))
      (node (ref "U$1") (pin "29-TX7") (pinfunction "29-TX7_29-TX7") (pintype "bidirectional"))
      (node (ref "U6") (pin "42") (pinfunction "GPS_RXDO_42") (pintype "input"))
    )
    (net (code "74") (name "UART5_TXD") (class "Default")
      (node (ref "J14") (pin "4") (pinfunction "4_4") (pintype "passive"))
      (node (ref "U$1") (pin "28-RX7") (pinfunction "28-RX7_28-RX7") (pintype "bidirectional"))
      (node (ref "U6") (pin "44") (pinfunction "GPS_TXD0_44") (pintype "output"))
    )
    (net (code "75") (name "UART6_RX") (class "Default")
      (node (ref "U$1") (pin "7-RX2/OUT1A") (pinfunction "7-RX2/OUT1A_7-RX2/OUT1A") (pintype "bidirectional"))
      (node (ref "X1") (pin "8") (pinfunction "P$8_8") (pintype "bidirectional"))
    )
    (net (code "76") (name "UART6_TX") (class "Default")
      (node (ref "U$1") (pin "8-TX2/IN1") (pinfunction "8-TX2/IN1_8-TX2/IN1") (pintype "bidirectional"))
      (node (ref "X1") (pin "10") (pinfunction "P$10_10") (pintype "bidirectional"))
    )
    (net (code "77") (name "USB_DEV_D+") (class "Default")
      (node (ref "J12") (pin "4") (pinfunction "4_4") (pintype "passive"))
      (node (ref "U$1") (pin "D+") (pinfunction "D+_D+") (pintype "bidirectional"))
    )
    (net (code "78") (name "USB_DEV_D-") (class "Default")
      (node (ref "J12") (pin "3") (pinfunction "3_3") (pintype "passive"))
      (node (ref "U$1") (pin "D-") (pinfunction "D-_D-") (pintype "bidirectional"))
    )
    (net (code "79") (name "USB_HOST_D+") (class "Default")
      (node (ref "J13") (pin "1") (pinfunction "1_1") (pintype "passive"))
      (node (ref "U$1") (pin "DP") (pinfunction "DP_DP") (pintype "bidirectional"))
    )
    (net (code "80") (name "USB_HOST_D-") (class "Default")
      (node (ref "J13") (pin "2") (pinfunction "2_2") (pintype "passive"))
      (node (ref "U$1") (pin "DM") (pinfunction "DM_DM") (pintype "bidirectional"))
    )
    (net (code "81") (name "unconnected-(H1-Pad1.9)") (class "Default")
      (node (ref "H1") (pin "1.9") (pinfunction "1.9_1.9") (pintype "bidirectional"))
    )
    (net (code "82") (name "unconnected-(H1-Pad1.10)") (class "Default")
      (node (ref "H1") (pin "1.10") (pinfunction "1.10_1.10") (pintype "bidirectional"))
    )
    (net (code "83") (name "unconnected-(H1-Pad1.11)") (class "Default")
      (node (ref "H1") (pin "1.11") (pinfunction "1.11_1.11") (pintype "bidirectional"))
    )
    (net (code "84") (name "unconnected-(H1-Pad1.12)") (class "Default")
      (node (ref "H1") (pin "1.12") (pinfunction "1.12_1.12") (pintype "bidirectional"))
    )
    (net (code "85") (name "unconnected-(H1-Pad1.13)") (class "Default")
      (node (ref "H1") (pin "1.13") (pinfunction "1.13_1.13") (pintype "bidirectional"))
    )
    (net (code "86") (name "unconnected-(H1-Pad1.14)") (class "Default")
      (node (ref "H1") (pin "1.14") (pinfunction "1.14_1.14") (pintype "bidirectional"))
    )
    (net (code "87") (name "unconnected-(H1-Pad1.15)") (class "Default")
      (node (ref "H1") (pin "1.15") (pinfunction "1.15_1.15") (pintype "bidirectional"))
    )
    (net (code "88") (name "unconnected-(H1-Pad1.16)") (class "Default")
      (node (ref "H1") (pin "1.16") (pinfunction "1.16_1.16") (pintype "bidirectional"))
    )
    (net (code "89") (name "unconnected-(H1-Pad1.17)") (class "Default")
      (node (ref "H1") (pin "1.17") (pinfunction "1.17_1.17") (pintype "bidirectional"))
    )
    (net (code "90") (name "unconnected-(H1-Pad1.18)") (class "Default")
      (node (ref "H1") (pin "1.18") (pinfunction "1.18_1.18") (pintype "bidirectional"))
    )
    (net (code "91") (name "unconnected-(H1-Pad1.19)") (class "Default")
      (node (ref "H1") (pin "1.19") (pinfunction "1.19_1.19") (pintype "bidirectional"))
    )
    (net (code "92") (name "unconnected-(H1-Pad1.20)") (class "Default")
      (node (ref "H1") (pin "1.20") (pinfunction "1.20_1.20") (pintype "bidirectional"))
    )
    (net (code "93") (name "unconnected-(H1-Pad1.21)") (class "Default")
      (node (ref "H1") (pin "1.21") (pinfunction "1.21_1.21") (pintype "bidirectional"))
    )
    (net (code "94") (name "unconnected-(H1-Pad1.22)") (class "Default")
      (node (ref "H1") (pin "1.22") (pinfunction "1.22_1.22") (pintype "bidirectional"))
    )
    (net (code "95") (name "unconnected-(H1-Pad1.23)") (class "Default")
      (node (ref "H1") (pin "1.23") (pinfunction "1.23_1.23") (pintype "bidirectional"))
    )
    (net (code "96") (name "unconnected-(H1-Pad1.24)") (class "Default")
      (node (ref "H1") (pin "1.24") (pinfunction "1.24_1.24") (pintype "bidirectional"))
    )
    (net (code "97") (name "unconnected-(H1-Pad1.25)") (class "Default")
      (node (ref "H1") (pin "1.25") (pinfunction "1.25_1.25") (pintype "bidirectional"))
    )
    (net (code "98") (name "unconnected-(H1-Pad1.26)") (class "Default")
      (node (ref "H1") (pin "1.26") (pinfunction "1.26_1.26") (pintype "bidirectional"))
    )
    (net (code "99") (name "unconnected-(H1-Pad1.27)") (class "Default")
      (node (ref "H1") (pin "1.27") (pinfunction "1.27_1.27") (pintype "bidirectional"))
    )
    (net (code "100") (name "unconnected-(H1-Pad1.28)") (class "Default")
      (node (ref "H1") (pin "1.28") (pinfunction "1.28_1.28") (pintype "bidirectional"))
    )
    (net (code "101") (name "unconnected-(H1-Pad1.29)") (class "Default")
      (node (ref "H1") (pin "1.29") (pinfunction "1.29_1.29") (pintype "bidirectional"))
    )
    (net (code "102") (name "unconnected-(H1-Pad1.30)") (class "Default")
      (node (ref "H1") (pin "1.30") (pinfunction "1.30_1.30") (pintype "bidirectional"))
    )
    (net (code "103") (name "unconnected-(H1-Pad1.31)") (class "Default")
      (node (ref "H1") (pin "1.31") (pinfunction "1.31_1.31") (pintype "bidirectional"))
    )
    (net (code "104") (name "unconnected-(H1-Pad1.32)") (class "Default")
      (node (ref "H1") (pin "1.32") (pinfunction "1.32_1.32") (pintype "bidirectional"))
    )
    (net (code "105") (name "unconnected-(H1-Pad1.33)") (class "Default")
      (node (ref "H1") (pin "1.33") (pinfunction "1.33_1.33") (pintype "bidirectional"))
    )
    (net (code "106") (name "unconnected-(H1-Pad1.34)") (class "Default")
      (node (ref "H1") (pin "1.34") (pinfunction "1.34_1.34") (pintype "bidirectional"))
    )
    (net (code "107") (name "unconnected-(H1-Pad1.35)") (class "Default")
      (node (ref "H1") (pin "1.35") (pinfunction "1.35_1.35") (pintype "bidirectional"))
    )
    (net (code "108") (name "unconnected-(H1-Pad1.36)") (class "Default")
      (node (ref "H1") (pin "1.36") (pinfunction "1.36_1.36") (pintype "bidirectional"))
    )
    (net (code "109") (name "unconnected-(H1-Pad1.37)") (class "Default")
      (node (ref "H1") (pin "1.37") (pinfunction "1.37_1.37") (pintype "bidirectional"))
    )
    (net (code "110") (name "unconnected-(H1-Pad1.38)") (class "Default")
      (node (ref "H1") (pin "1.38") (pinfunction "1.38_1.38") (pintype "bidirectional"))
    )
    (net (code "111") (name "unconnected-(H1-Pad1.39)") (class "Default")
      (node (ref "H1") (pin "1.39") (pinfunction "1.39_1.39") (pintype "bidirectional"))
    )
    (net (code "112") (name "unconnected-(H1-Pad1.40)") (class "Default")
      (node (ref "H1") (pin "1.40") (pinfunction "1.40_1.40") (pintype "bidirectional"))
    )
    (net (code "113") (name "unconnected-(H1-Pad1.42)") (class "Default")
      (node (ref "H1") (pin "1.42") (pinfunction "1.42_1.42") (pintype "bidirectional"))
    )
    (net (code "114") (name "unconnected-(H1-Pad1.44)") (class "Default")
      (node (ref "H1") (pin "1.44") (pinfunction "1.44_1.44") (pintype "bidirectional"))
    )
    (net (code "115") (name "unconnected-(H1-Pad1.45)") (class "Default")
      (node (ref "H1") (pin "1.45") (pinfunction "1.45_1.45") (pintype "bidirectional"))
    )
    (net (code "116") (name "unconnected-(H1-Pad1.46)") (class "Default")
      (node (ref "H1") (pin "1.46") (pinfunction "1.46_1.46") (pintype "bidirectional"))
    )
    (net (code "117") (name "unconnected-(H1-Pad1.47)") (class "Default")
      (node (ref "H1") (pin "1.47") (pinfunction "1.47_1.47") (pintype "bidirectional"))
    )
    (net (code "118") (name "unconnected-(H1-Pad1.48)") (class "Default")
      (node (ref "H1") (pin "1.48") (pinfunction "1.48_1.48") (pintype "bidirectional"))
    )
    (net (code "119") (name "unconnected-(H1-Pad1.49)") (class "Default")
      (node (ref "H1") (pin "1.49") (pinfunction "1.49_1.49") (pintype "bidirectional"))
    )
    (net (code "120") (name "unconnected-(H1-Pad1.50)") (class "Default")
      (node (ref "H1") (pin "1.50") (pinfunction "1.50_1.50") (pintype "bidirectional"))
    )
    (net (code "121") (name "unconnected-(H1-Pad1.51)") (class "Default")
      (node (ref "H1") (pin "1.51") (pinfunction "1.51_1.51") (pintype "bidirectional"))
    )
    (net (code "122") (name "unconnected-(H1-Pad1.52)") (class "Default")
      (node (ref "H1") (pin "1.52") (pinfunction "1.52_1.52") (pintype "bidirectional"))
    )
    (net (code "123") (name "unconnected-(H1-Pad2.5)") (class "Default")
      (node (ref "H1") (pin "2.5") (pinfunction "2.5_2.5") (pintype "bidirectional"))
    )
    (net (code "124") (name "unconnected-(H1-Pad2.6)") (class "Default")
      (node (ref "H1") (pin "2.6") (pinfunction "2.6_2.6") (pintype "bidirectional"))
    )
    (net (code "125") (name "unconnected-(H1-Pad2.8)") (class "Default")
      (node (ref "H1") (pin "2.8") (pinfunction "2.8_2.8") (pintype "bidirectional"))
    )
    (net (code "126") (name "unconnected-(H1-Pad2.9)") (class "Default")
      (node (ref "H1") (pin "2.9") (pinfunction "2.9_2.9") (pintype "bidirectional"))
    )
    (net (code "127") (name "unconnected-(H1-Pad2.10)") (class "Default")
      (node (ref "H1") (pin "2.10") (pinfunction "2.10_2.10") (pintype "bidirectional"))
    )
    (net (code "128") (name "unconnected-(H1-Pad2.11)") (class "Default")
      (node (ref "H1") (pin "2.11") (pinfunction "2.11_2.11") (pintype "bidirectional"))
    )
    (net (code "129") (name "unconnected-(H1-Pad2.12)") (class "Default")
      (node (ref "H1") (pin "2.12") (pinfunction "2.12_2.12") (pintype "bidirectional"))
    )
    (net (code "130") (name "unconnected-(H1-Pad2.13)") (class "Default")
      (node (ref "H1") (pin "2.13") (pinfunction "2.13_2.13") (pintype "bidirectional"))
    )
    (net (code "131") (name "unconnected-(H1-Pad2.15)") (class "Default")
      (node (ref "H1") (pin "2.15") (pinfunction "2.15_2.15") (pintype "bidirectional"))
    )
    (net (code "132") (name "unconnected-(H1-Pad2.16)") (class "Default")
      (node (ref "H1") (pin "2.16") (pinfunction "2.16_2.16") (pintype "bidirectional"))
    )
    (net (code "133") (name "unconnected-(H1-Pad2.18)") (class "Default")
      (node (ref "H1") (pin "2.18") (pinfunction "2.18_2.18") (pintype "bidirectional"))
    )
    (net (code "134") (name "unconnected-(H1-Pad2.19)") (class "Default")
      (node (ref "H1") (pin "2.19") (pinfunction "2.19_2.19") (pintype "bidirectional"))
    )
    (net (code "135") (name "unconnected-(H1-Pad2.23)") (class "Default")
      (node (ref "H1") (pin "2.23") (pinfunction "2.23_2.23") (pintype "bidirectional"))
    )
    (net (code "136") (name "unconnected-(H1-Pad2.24)") (class "Default")
      (node (ref "H1") (pin "2.24") (pinfunction "2.24_2.24") (pintype "bidirectional"))
    )
    (net (code "137") (name "unconnected-(H1-Pad2.31)") (class "Default")
      (node (ref "H1") (pin "2.31") (pinfunction "2.31_2.31") (pintype "bidirectional"))
    )
    (net (code "138") (name "unconnected-(H1-Pad2.33)") (class "Default")
      (node (ref "H1") (pin "2.33") (pinfunction "2.33_2.33") (pintype "bidirectional"))
    )
    (net (code "139") (name "unconnected-(H1-Pad2.34)") (class "Default")
      (node (ref "H1") (pin "2.34") (pinfunction "2.34_2.34") (pintype "bidirectional"))
    )
    (net (code "140") (name "unconnected-(H1-Pad2.35)") (class "Default")
      (node (ref "H1") (pin "2.35") (pinfunction "2.35_2.35") (pintype "bidirectional"))
    )
    (net (code "141") (name "unconnected-(H1-Pad2.36)") (class "Default")
      (node (ref "H1") (pin "2.36") (pinfunction "2.36_2.36") (pintype "bidirectional"))
    )
    (net (code "142") (name "unconnected-(H1-Pad2.37)") (class "Default")
      (node (ref "H1") (pin "2.37") (pinfunction "2.37_2.37") (pintype "bidirectional"))
    )
    (net (code "143") (name "unconnected-(H1-Pad2.38)") (class "Default")
      (node (ref "H1") (pin "2.38") (pinfunction "2.38_2.38") (pintype "bidirectional"))
    )
    (net (code "144") (name "unconnected-(H1-Pad2.39)") (class "Default")
      (node (ref "H1") (pin "2.39") (pinfunction "2.39_2.39") (pintype "bidirectional"))
    )
    (net (code "145") (name "unconnected-(H1-Pad2.40)") (class "Default")
      (node (ref "H1") (pin "2.40") (pinfunction "2.40_2.40") (pintype "bidirectional"))
    )
    (net (code "146") (name "unconnected-(H1-Pad2.41)") (class "Default")
      (node (ref "H1") (pin "2.41") (pinfunction "2.41_2.41") (pintype "bidirectional"))
    )
    (net (code "147") (name "unconnected-(H1-Pad2.42)") (class "Default")
      (node (ref "H1") (pin "2.42") (pinfunction "2.42_2.42") (pintype "bidirectional"))
    )
    (net (code "148") (name "unconnected-(H1-Pad2.43)") (class "Default")
      (node (ref "H1") (pin "2.43") (pinfunction "2.43_2.43") (pintype "bidirectional"))
    )
    (net (code "149") (name "unconnected-(H1-Pad2.44)") (class "Default")
      (node (ref "H1") (pin "2.44") (pinfunction "2.44_2.44") (pintype "bidirectional"))
    )
    (net (code "150") (name "unconnected-(H1-Pad2.45)") (class "Default")
      (node (ref "H1") (pin "2.45") (pinfunction "2.45_2.45") (pintype "bidirectional"))
    )
    (net (code "151") (name "unconnected-(H1-Pad2.46)") (class "Default")
      (node (ref "H1") (pin "2.46") (pinfunction "2.46_2.46") (pintype "bidirectional"))
    )
    (net (code "152") (name "unconnected-(H1-Pad2.49)") (class "Default")
      (node (ref "H1") (pin "2.49") (pinfunction "2.49_2.49") (pintype "bidirectional"))
    )
    (net (code "153") (name "unconnected-(H1-Pad2.50)") (class "Default")
      (node (ref "H1") (pin "2.50") (pinfunction "2.50_2.50") (pintype "bidirectional"))
    )
    (net (code "154") (name "unconnected-(H1-Pad2.51)") (class "Default")
      (node (ref "H1") (pin "2.51") (pinfunction "2.51_2.51") (pintype "bidirectional"))
    )
    (net (code "155") (name "unconnected-(H1-Pad2.52)") (class "Default")
      (node (ref "H1") (pin "2.52") (pinfunction "2.52_2.52") (pintype "bidirectional"))
    )
    (net (code "156") (name "unconnected-(H1-PadP$1)") (class "Default")
      (node (ref "H1") (pin "P$1") (pinfunction "P$1_P$1") (pintype "bidirectional"))
    )
    (net (code "157") (name "unconnected-(H1-PadP$2)") (class "Default")
      (node (ref "H1") (pin "P$2") (pinfunction "P$2_P$2") (pintype "bidirectional"))
    )
    (net (code "158") (name "unconnected-(H1-PadP$3)") (class "Default")
      (node (ref "H1") (pin "P$3") (pinfunction "P$3_P$3") (pintype "bidirectional"))
    )
    (net (code "159") (name "unconnected-(U$1-PadON{slash}OFF)") (class "Default")
      (node (ref "U$1") (pin "ON/OFF") (pinfunction "ON/OFF_ON/OFF") (pintype "bidirectional"))
    )
    (net (code "160") (name "unconnected-(U1-NC-Pad7)") (class "Default")
      (node (ref "U1") (pin "7") (pinfunction "NC_7") (pintype "no_connect"))
    )
    (net (code "161") (name "unconnected-(U1-NC_2-Pad2)") (class "Default")
      (node (ref "U1") (pin "2") (pinfunction "NC_2_2") (pintype "no_connect"))
    )
    (net (code "162") (name "unconnected-(U1-NC_3-Pad3)") (class "Default")
      (node (ref "U1") (pin "3") (pinfunction "NC_3_3") (pintype "no_connect"))
    )
    (net (code "163") (name "unconnected-(U1-NC_4-Pad6)") (class "Default")
      (node (ref "U1") (pin "6") (pinfunction "NC_4_6") (pintype "no_connect"))
    )
    (net (code "164") (name "unconnected-(U3-GPIO_2-Pad16)") (class "Default")
      (node (ref "U3") (pin "16") (pinfunction "GPIO_2_16") (pintype "bidirectional"))
    )
    (net (code "165") (name "unconnected-(U4-DIO0-Pad14)") (class "Default")
      (node (ref "U4") (pin "14") (pinfunction "DIO0_14") (pintype "bidirectional"))
    )
    (net (code "166") (name "unconnected-(U4-DIO2-Pad16)") (class "Default")
      (node (ref "U4") (pin "16") (pinfunction "DIO2_16") (pintype "bidirectional"))
    )
    (net (code "167") (name "unconnected-(U4-DIO3-Pad11)") (class "Default")
      (node (ref "U4") (pin "11") (pinfunction "DIO3_11") (pintype "bidirectional"))
    )
    (net (code "168") (name "unconnected-(U4-DIO4-Pad12)") (class "Default")
      (node (ref "U4") (pin "12") (pinfunction "DIO4_12") (pintype "bidirectional"))
    )
    (net (code "169") (name "unconnected-(U4-DIO5-Pad7)") (class "Default")
      (node (ref "U4") (pin "7") (pinfunction "DIO5_7") (pintype "bidirectional"))
    )
    (net (code "170") (name "unconnected-(U5-Pad1)") (class "Default")
      (node (ref "U5") (pin "1") (pinfunction "1_1") (pintype "passive"))
    )
    (net (code "171") (name "unconnected-(U6-P$3-Pad3)") (class "Default")
      (node (ref "U6") (pin "3") (pinfunction "P$3_3") (pintype "bidirectional"))
    )
    (net (code "172") (name "unconnected-(U6-P$4-Pad4)") (class "Default")
      (node (ref "U6") (pin "4") (pinfunction "P$4_4") (pintype "bidirectional"))
    )
    (net (code "173") (name "unconnected-(U6-P$5-Pad5)") (class "Default")
      (node (ref "U6") (pin "5") (pinfunction "P$5_5") (pintype "bidirectional"))
    )
    (net (code "174") (name "unconnected-(U6-P$6-Pad6)") (class "Default")
      (node (ref "U6") (pin "6") (pinfunction "P$6_6") (pintype "bidirectional"))
    )
    (net (code "175") (name "unconnected-(U6-P$8-Pad8)") (class "Default")
      (node (ref "U6") (pin "8") (pinfunction "P$8_8") (pintype "bidirectional"))
    )
    (net (code "176") (name "unconnected-(U6-P$12-Pad12)") (class "Default")
      (node (ref "U6") (pin "12") (pinfunction "P$12_12") (pintype "bidirectional"))
    )
    (net (code "177") (name "unconnected-(U6-P$13-Pad13)") (class "Default")
      (node (ref "U6") (pin "13") (pinfunction "P$13_13") (pintype "bidirectional"))
    )
    (net (code "178") (name "unconnected-(U6-P$14-Pad14)") (class "Default")
      (node (ref "U6") (pin "14") (pinfunction "P$14_14") (pintype "bidirectional"))
    )
    (net (code "179") (name "unconnected-(U6-P$16-Pad16)") (class "Default")
      (node (ref "U6") (pin "16") (pinfunction "P$16_16") (pintype "bidirectional"))
    )
    (net (code "180") (name "unconnected-(U6-P$17-Pad17)") (class "Default")
      (node (ref "U6") (pin "17") (pinfunction "P$17_17") (pintype "bidirectional"))
    )
    (net (code "181") (name "unconnected-(U6-P$20-Pad20)") (class "Default")
      (node (ref "U6") (pin "20") (pinfunction "P$20_20") (pintype "bidirectional"))
    )
    (net (code "182") (name "unconnected-(U6-P$23-Pad23)") (class "Default")
      (node (ref "U6") (pin "23") (pinfunction "P$23_23") (pintype "bidirectional"))
    )
    (net (code "183") (name "unconnected-(U6-P$26-Pad26)") (class "Default")
      (node (ref "U6") (pin "26") (pinfunction "P$26_26") (pintype "bidirectional"))
    )
    (net (code "184") (name "unconnected-(U6-P$30-Pad30)") (class "Default")
      (node (ref "U6") (pin "30") (pinfunction "P$30_30") (pintype "bidirectional"))
    )
    (net (code "185") (name "unconnected-(U6-P$34-Pad34)") (class "Default")
      (node (ref "U6") (pin "34") (pinfunction "P$34_34") (pintype "bidirectional"))
    )
    (net (code "186") (name "unconnected-(U6-P$35-Pad35)") (class "Default")
      (node (ref "U6") (pin "35") (pinfunction "P$35_35") (pintype "bidirectional"))
    )
    (net (code "187") (name "unconnected-(U6-P$36-Pad36)") (class "Default")
      (node (ref "U6") (pin "36") (pinfunction "P$36_36") (pintype "bidirectional"))
    )
    (net (code "188") (name "unconnected-(U6-P$37-Pad37)") (class "Default")
      (node (ref "U6") (pin "37") (pinfunction "P$37_37") (pintype "bidirectional"))
    )
    (net (code "189") (name "unconnected-(U6-P$38-Pad38)") (class "Default")
      (node (ref "U6") (pin "38") (pinfunction "P$38_38") (pintype "bidirectional"))
    )
    (net (code "190") (name "unconnected-(U6-P$39-Pad39)") (class "Default")
      (node (ref "U6") (pin "39") (pinfunction "P$39_39") (pintype "bidirectional"))
    )
    (net (code "191") (name "unconnected-(U6-P$40-Pad40)") (class "Default")
      (node (ref "U6") (pin "40") (pinfunction "P$40_40") (pintype "bidirectional"))
    )
    (net (code "192") (name "unconnected-(U6-P$41-Pad41)") (class "Default")
      (node (ref "U6") (pin "41") (pinfunction "P$41_41") (pintype "bidirectional"))
    )
    (net (code "193") (name "unconnected-(U6-P$43-Pad43)") (class "Default")
      (node (ref "U6") (pin "43") (pinfunction "P$43_43") (pintype "bidirectional"))
    )
    (net (code "194") (name "unconnected-(U6-P$45-Pad45)") (class "Default")
      (node (ref "U6") (pin "45") (pinfunction "P$45_45") (pintype "bidirectional"))
    )
    (net (code "195") (name "unconnected-(U6-P$46-Pad46)") (class "Default")
      (node (ref "U6") (pin "46") (pinfunction "P$46_46") (pintype "bidirectional"))
    )
    (net (code "196") (name "unconnected-(U6-P$47-Pad47)") (class "Default")
      (node (ref "U6") (pin "47") (pinfunction "P$47_47") (pintype "bidirectional"))
    )
    (net (code "197") (name "unconnected-(U6-P$48-Pad48)") (class "Default")
      (node (ref "U6") (pin "48") (pinfunction "P$48_48") (pintype "bidirectional"))
    )
    (net (code "198") (name "unconnected-(U6-P$49-Pad49)") (class "Default")
      (node (ref "U6") (pin "49") (pinfunction "P$49_49") (pintype "bidirectional"))
    )
    (net (code "199") (name "unconnected-(U6-P$50-Pad50)") (class "Default")
      (node (ref "U6") (pin "50") (pinfunction "P$50_50") (pintype "bidirectional"))
    )
    (net (code "200") (name "unconnected-(U6-P$51-Pad51)") (class "Default")
      (node (ref "U6") (pin "51") (pinfunction "P$51_51") (pintype "bidirectional"))
    )
    (net (code "201") (name "unconnected-(U6-P$52-Pad52)") (class "Default")
      (node (ref "U6") (pin "52") (pinfunction "P$52_52") (pintype "bidirectional"))
    )
    (net (code "202") (name "unconnected-(U6-P$53-Pad53)") (class "Default")
      (node (ref "U6") (pin "53") (pinfunction "P$53_53") (pintype "bidirectional"))
    )
    (net (code "203") (name "unconnected-(U6-P$54-Pad54)") (class "Default")
      (node (ref "U6") (pin "54") (pinfunction "P$54_54") (pintype "bidirectional"))
    )
    (net (code "204") (name "unconnected-(U6-P$55-Pad55)") (class "Default")
      (node (ref "U6") (pin "55") (pinfunction "P$55_55") (pintype "bidirectional"))
    )
    (net (code "205") (name "unconnected-(U6-P$56-Pad56)") (class "Default")
      (node (ref "U6") (pin "56") (pinfunction "P$56_56") (pintype "bidirectional"))
    )
    (net (code "206") (name "unconnected-(U6-P$57-Pad57)") (class "Default")
      (node (ref "U6") (pin "57") (pinfunction "P$57_57") (pintype "bidirectional"))
    )
    (net (code "207") (name "unconnected-(U6-P$59-Pad59)") (class "Default")
      (node (ref "U6") (pin "59") (pinfunction "P$59_59") (pintype "bidirectional"))
    )
    (net (code "208") (name "unconnected-(U6-P$60-Pad60)") (class "Default")
      (node (ref "U6") (pin "60") (pinfunction "P$60_60") (pintype "bidirectional"))
    )
    (net (code "209") (name "unconnected-(U6-P$61-Pad61)") (class "Default")
      (node (ref "U6") (pin "61") (pinfunction "P$61_61") (pintype "bidirectional"))
    )
    (net (code "210") (name "unconnected-(U6-P$62-Pad62)") (class "Default")
      (node (ref "U6") (pin "62") (pinfunction "P$62_62") (pintype "bidirectional"))
    )
    (net (code "211") (name "unconnected-(U6-P$63-Pad63)") (class "Default")
      (node (ref "U6") (pin "63") (pinfunction "P$63_63") (pintype "bidirectional"))
    )
    (net (code "212") (name "unconnected-(U6-P$65-Pad65)") (class "Default")
      (node (ref "U6") (pin "65") (pinfunction "P$65_65") (pintype "bidirectional"))
    )
    (net (code "213") (name "unconnected-(U6-P$66-Pad66)") (class "Default")
      (node (ref "U6") (pin "66") (pinfunction "P$66_66") (pintype "bidirectional"))
    )
    (net (code "214") (name "unconnected-(U6-P$67-Pad67)") (class "Default")
      (node (ref "U6") (pin "67") (pinfunction "P$67_67") (pintype "bidirectional"))
    )
    (net (code "215") (name "unconnected-(U6-P$68-Pad68)") (class "Default")
      (node (ref "U6") (pin "68") (pinfunction "P$68_68") (pintype "bidirectional"))
    )
    (net (code "216") (name "unconnected-(U6-P$69-Pad69)") (class "Default")
      (node (ref "U6") (pin "69") (pinfunction "P$69_69") (pintype "bidirectional"))
    )
    (net (code "217") (name "unconnected-(X1-P$1-Pad1)") (class "Default")
      (node (ref "X1") (pin "1") (pinfunction "P$1_1") (pintype "bidirectional"))
    )
    (net (code "218") (name "unconnected-(X1-P$4-Pad4)") (class "Default")
      (node (ref "X1") (pin "4") (pinfunction "P$4_4") (pintype "bidirectional"))
    )
    (net (code "219") (name "unconnected-(X1-P$6-Pad6)") (class "Default")
      (node (ref "X1") (pin "6") (pinfunction "P$6_6") (pintype "bidirectional"))
    )
    (net (code "220") (name "unconnected-(X1-P$7-Pad7)") (class "Default")
      (node (ref "X1") (pin "7") (pinfunction "P$7_7") (pintype "bidirectional"))
    )
    (net (code "221") (name "unconnected-(X1-P$9-Pad9)") (class "Default")
      (node (ref "X1") (pin "9") (pinfunction "P$9_9") (pintype "bidirectional"))
    )
    (net (code "222") (name "unconnected-(X1-P$12-Pad12)") (class "Default")
      (node (ref "X1") (pin "12") (pinfunction "P$12_12") (pintype "bidirectional"))
    )
    (net (code "223") (name "unconnected-(X1-P$14-Pad14)") (class "Default")
      (node (ref "X1") (pin "14") (pinfunction "P$14_14") (pintype "bidirectional"))
    )
    (net (code "224") (name "unconnected-(X1-P$17-Pad17)") (class "Default")
      (node (ref "X1") (pin "17") (pinfunction "P$17_17") (pintype "bidirectional"))
    )
    (net (code "225") (name "unconnected-(X1-P$20-Pad20)") (class "Default")
      (node (ref "X1") (pin "20") (pinfunction "P$20_20") (pintype "bidirectional"))
    )
    (net (code "226") (name "unconnected-(X1-P$25-Pad25)") (class "Default")
      (node (ref "X1") (pin "25") (pinfunction "P$25_25") (pintype "bidirectional"))
    )
    (net (code "227") (name "unconnected-(X1-P$27-Pad27)") (class "Default")
      (node (ref "X1") (pin "27") (pinfunction "P$27_27") (pintype "bidirectional"))
    )
    (net (code "228") (name "unconnected-(X1-P$28-Pad28)") (class "Default")
      (node (ref "X1") (pin "28") (pinfunction "P$28_28") (pintype "bidirectional"))
    )
    (net (code "229") (name "unconnected-(X1-P$29-Pad29)") (class "Default")
      (node (ref "X1") (pin "29") (pinfunction "P$29_29") (pintype "bidirectional"))
    )
    (net (code "230") (name "unconnected-(X1-P$30-Pad30)") (class "Default")
      (node (ref "X1") (pin "30") (pinfunction "P$30_30") (pintype "bidirectional"))
    )
    (net (code "231") (name "unconnected-(X1-P$31-Pad31)") (class "Default")
      (node (ref "X1") (pin "31") (pinfunction "P$31_31") (pintype "bidirectional"))
    )
    (net (code "232") (name "unconnected-(X1-P$32-Pad32)") (class "Default")
      (node (ref "X1") (pin "32") (pinfunction "P$32_32") (pintype "bidirectional"))
    )
    (net (code "233") (name "unconnected-(X1-P$33-Pad33)") (class "Default")
      (node (ref "X1") (pin "33") (pinfunction "P$33_33") (pintype "bidirectional"))
    )
    (net (code "234") (name "unconnected-(X1-P$34-Pad34)") (class "Default")
      (node (ref "X1") (pin "34") (pinfunction "P$34_34") (pintype "bidirectional"))
    )
    (net (code "235") (name "unconnected-(X1-P$35-Pad35)") (class "Default")
      (node (ref "X1") (pin "35") (pinfunction "P$35_35") (pintype "bidirectional"))
    )
    (net (code "236") (name "unconnected-(X1-P$36-Pad36)") (class "Default")
      (node (ref "X1") (pin "36") (pinfunction "P$36_36") (pintype "bidirectional"))
    )
    (net (code "237") (name "unconnected-(X1-P$37-Pad37)") (class "Default")
      (node (ref "X1") (pin "37") (pinfunction "P$37_37") (pintype "bidirectional"))
    )
    (net (code "238") (name "unconnected-(X1-P$38-Pad38)") (class "Default")
      (node (ref "X1") (pin "38") (pinfunction "P$38_38") (pintype "bidirectional"))
    )
    (net (code "239") (name "unconnected-(X1-P$40-Pad40)") (class "Default")
      (node (ref "X1") (pin "40") (pinfunction "P$40_40") (pintype "bidirectional"))
    )
    (net (code "240") (name "unconnected-(X2-Pad1)") (class "Default")
      (node (ref "X2") (pin "1") (pinfunction "1_1") (pintype "passive"))
    )
    (net (code "241") (name "unconnected-(X2AA-1-Pad33)") (class "Default")
      (node (ref "X2") (pin "33") (pinfunction "1_33") (pintype "passive"))
    )
    (net (code "242") (name "unconnected-(X2AB-1-Pad34)") (class "Default")
      (node (ref "X2") (pin "34") (pinfunction "1_34") (pintype "passive"))
    )
    (net (code "243") (name "unconnected-(X2AC-1-Pad35)") (class "Default")
      (node (ref "X2") (pin "35") (pinfunction "1_35") (pintype "passive"))
    )
    (net (code "244") (name "unconnected-(X2AD-1-Pad36)") (class "Default")
      (node (ref "X2") (pin "36") (pinfunction "1_36") (pintype "passive"))
    )
    (net (code "245") (name "unconnected-(X2AE-1-Pad37)") (class "Default")
      (node (ref "X2") (pin "37") (pinfunction "1_37") (pintype "passive"))
    )
    (net (code "246") (name "unconnected-(X2AF-1-Pad38)") (class "Default")
      (node (ref "X2") (pin "38") (pinfunction "1_38") (pintype "passive"))
    )
    (net (code "247") (name "unconnected-(X2AG-1-Pad39)") (class "Default")
      (node (ref "X2") (pin "39") (pinfunction "1_39") (pintype "passive"))
    )
    (net (code "248") (name "unconnected-(X2AH-1-Pad4)") (class "Default")
      (node (ref "X2") (pin "4") (pinfunction "1_4") (pintype "passive"))
    )
    (net (code "249") (name "unconnected-(X2AI-1-Pad40)") (class "Default")
      (node (ref "X2") (pin "40") (pinfunction "1_40") (pintype "passive"))
    )
    (net (code "250") (name "unconnected-(X2AJ-1-Pad5)") (class "Default")
      (node (ref "X2") (pin "5") (pinfunction "1_5") (pintype "passive"))
    )
    (net (code "251") (name "unconnected-(X2AK-1-Pad6)") (class "Default")
      (node (ref "X2") (pin "6") (pinfunction "1_6") (pintype "passive"))
    )
    (net (code "252") (name "unconnected-(X2AL-1-Pad7)") (class "Default")
      (node (ref "X2") (pin "7") (pinfunction "1_7") (pintype "passive"))
    )
    (net (code "253") (name "unconnected-(X2AM-1-Pad8)") (class "Default")
      (node (ref "X2") (pin "8") (pinfunction "1_8") (pintype "passive"))
    )
    (net (code "254") (name "unconnected-(X2AN-1-Pad9)") (class "Default")
      (node (ref "X2") (pin "9") (pinfunction "1_9") (pintype "passive"))
    )
    (net (code "255") (name "unconnected-(X2B-1-Pad10)") (class "Default")
      (node (ref "X2") (pin "10") (pinfunction "1_10") (pintype "passive"))
    )
    (net (code "256") (name "unconnected-(X2C-1-Pad11)") (class "Default")
      (node (ref "X2") (pin "11") (pinfunction "1_11") (pintype "passive"))
    )
    (net (code "257") (name "unconnected-(X2D-1-Pad12)") (class "Default")
      (node (ref "X2") (pin "12") (pinfunction "1_12") (pintype "passive"))
    )
    (net (code "258") (name "unconnected-(X2E-1-Pad13)") (class "Default")
      (node (ref "X2") (pin "13") (pinfunction "1_13") (pintype "passive"))
    )
    (net (code "259") (name "unconnected-(X2F-1-Pad14)") (class "Default")
      (node (ref "X2") (pin "14") (pinfunction "1_14") (pintype "passive"))
    )
    (net (code "260") (name "unconnected-(X2G-1-Pad15)") (class "Default")
      (node (ref "X2") (pin "15") (pinfunction "1_15") (pintype "passive"))
    )
    (net (code "261") (name "unconnected-(X2H-1-Pad16)") (class "Default")
      (node (ref "X2") (pin "16") (pinfunction "1_16") (pintype "passive"))
    )
    (net (code "262") (name "unconnected-(X2I-1-Pad17)") (class "Default")
      (node (ref "X2") (pin "17") (pinfunction "1_17") (pintype "passive"))
    )
    (net (code "263") (name "unconnected-(X2J-1-Pad18)") (class "Default")
      (node (ref "X2") (pin "18") (pinfunction "1_18") (pintype "passive"))
    )
    (net (code "264") (name "unconnected-(X2K-1-Pad19)") (class "Default")
      (node (ref "X2") (pin "19") (pinfunction "1_19") (pintype "passive"))
    )
    (net (code "265") (name "unconnected-(X2L-1-Pad2)") (class "Default")
      (node (ref "X2") (pin "2") (pinfunction "1_2") (pintype "passive"))
    )
    (net (code "266") (name "unconnected-(X2M-1-Pad20)") (class "Default")
      (node (ref "X2") (pin "20") (pinfunction "1_20") (pintype "passive"))
    )
    (net (code "267") (name "unconnected-(X2N-1-Pad21)") (class "Default")
      (node (ref "X2") (pin "21") (pinfunction "1_21") (pintype "passive"))
    )
    (net (code "268") (name "unconnected-(X2O-1-Pad22)") (class "Default")
      (node (ref "X2") (pin "22") (pinfunction "1_22") (pintype "passive"))
    )
    (net (code "269") (name "unconnected-(X2P-1-Pad23)") (class "Default")
      (node (ref "X2") (pin "23") (pinfunction "1_23") (pintype "passive"))
    )
    (net (code "270") (name "unconnected-(X2Q-1-Pad24)") (class "Default")
      (node (ref "X2") (pin "24") (pinfunction "1_24") (pintype "passive"))
    )
    (net (code "271") (name "unconnected-(X2R-1-Pad25)") (class "Default")
      (node (ref "X2") (pin "25") (pinfunction "1_25") (pintype "passive"))
    )
    (net (code "272") (name "unconnected-(X2S-1-Pad26)") (class "Default")
      (node (ref "X2") (pin "26") (pinfunction "1_26") (pintype "passive"))
    )
    (net (code "273") (name "unconnected-(X2T-1-Pad27)") (class "Default")
      (node (ref "X2") (pin "27") (pinfunction "1_27") (pintype "passive"))
    )
    (net (code "274") (name "unconnected-(X2U-1-Pad28)") (class "Default")
      (node (ref "X2") (pin "28") (pinfunction "1_28") (pintype "passive"))
    )
    (net (code "275") (name "unconnected-(X2V-1-Pad29)") (class "Default")
      (node (ref "X2") (pin "29") (pinfunction "1_29") (pintype "passive"))
    )
    (net (code "276") (name "unconnected-(X2W-1-Pad3)") (class "Default")
      (node (ref "X2") (pin "3") (pinfunction "1_3") (pintype "passive"))
    )
    (net (code "277") (name "unconnected-(X2X-1-Pad30)") (class "Default")
      (node (ref "X2") (pin "30") (pinfunction "1_30") (pintype "passive"))
    )
    (net (code "278") (name "unconnected-(X2Y-1-Pad31)") (class "Default")
      (node (ref "X2") (pin "31") (pinfunction "1_31") (pintype "passive"))
    )
    (net (code "279") (name "unconnected-(X2Z-1-Pad32)") (class "Default")
      (node (ref "X2") (pin "32") (pinfunction "1_32") (pintype "passive"))
    )
  )
)
